# mach_nhan_tin_hieu.net
KiCad netlist of a schematic drawn in Altium Designer
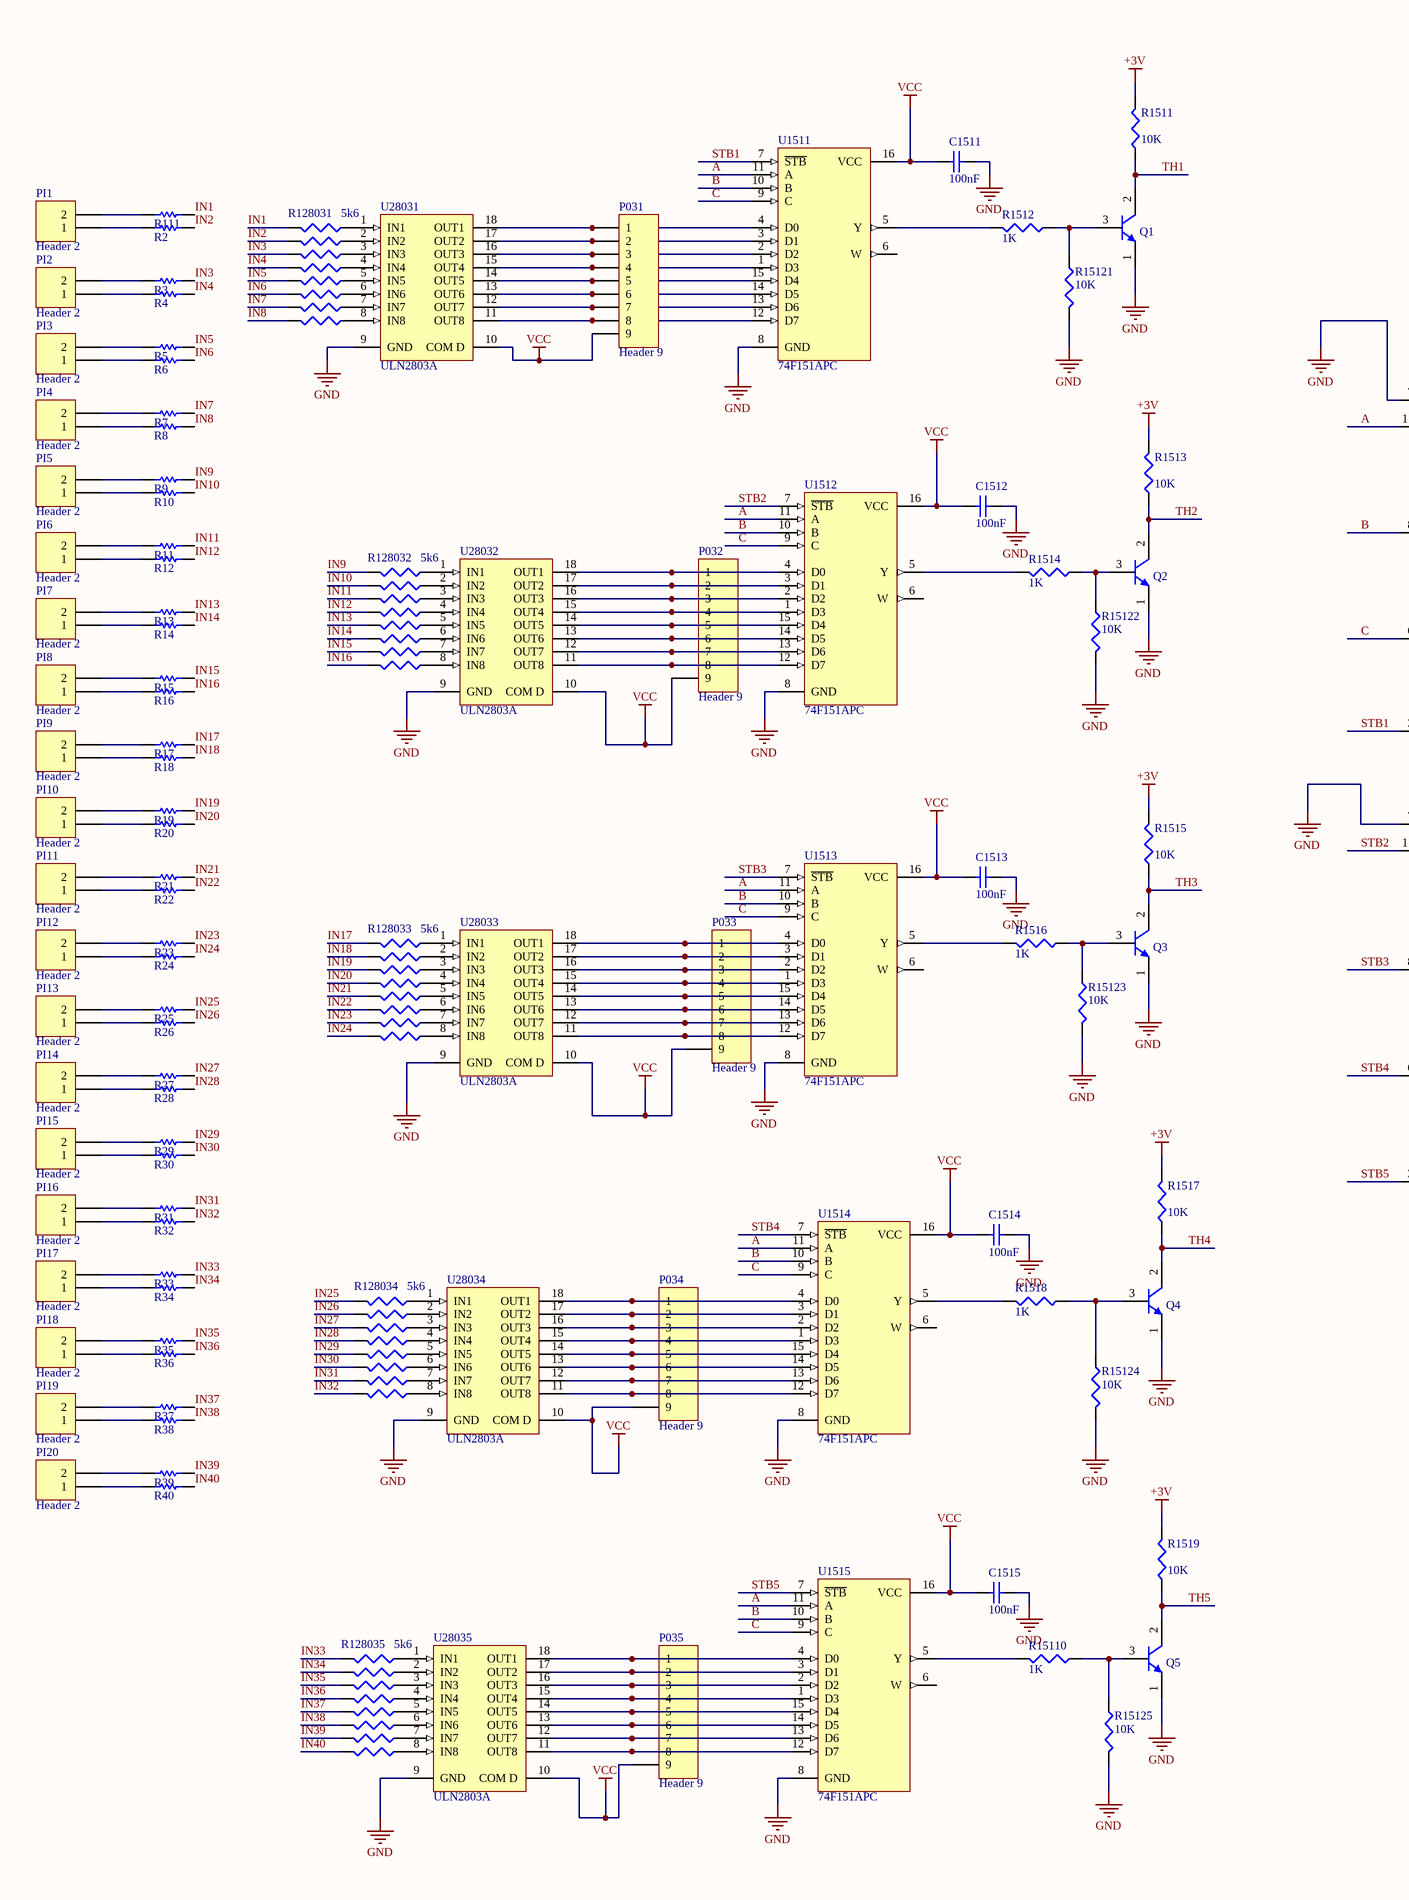
[diagram p0: mach nhan tin hieu.SchDoc, left]
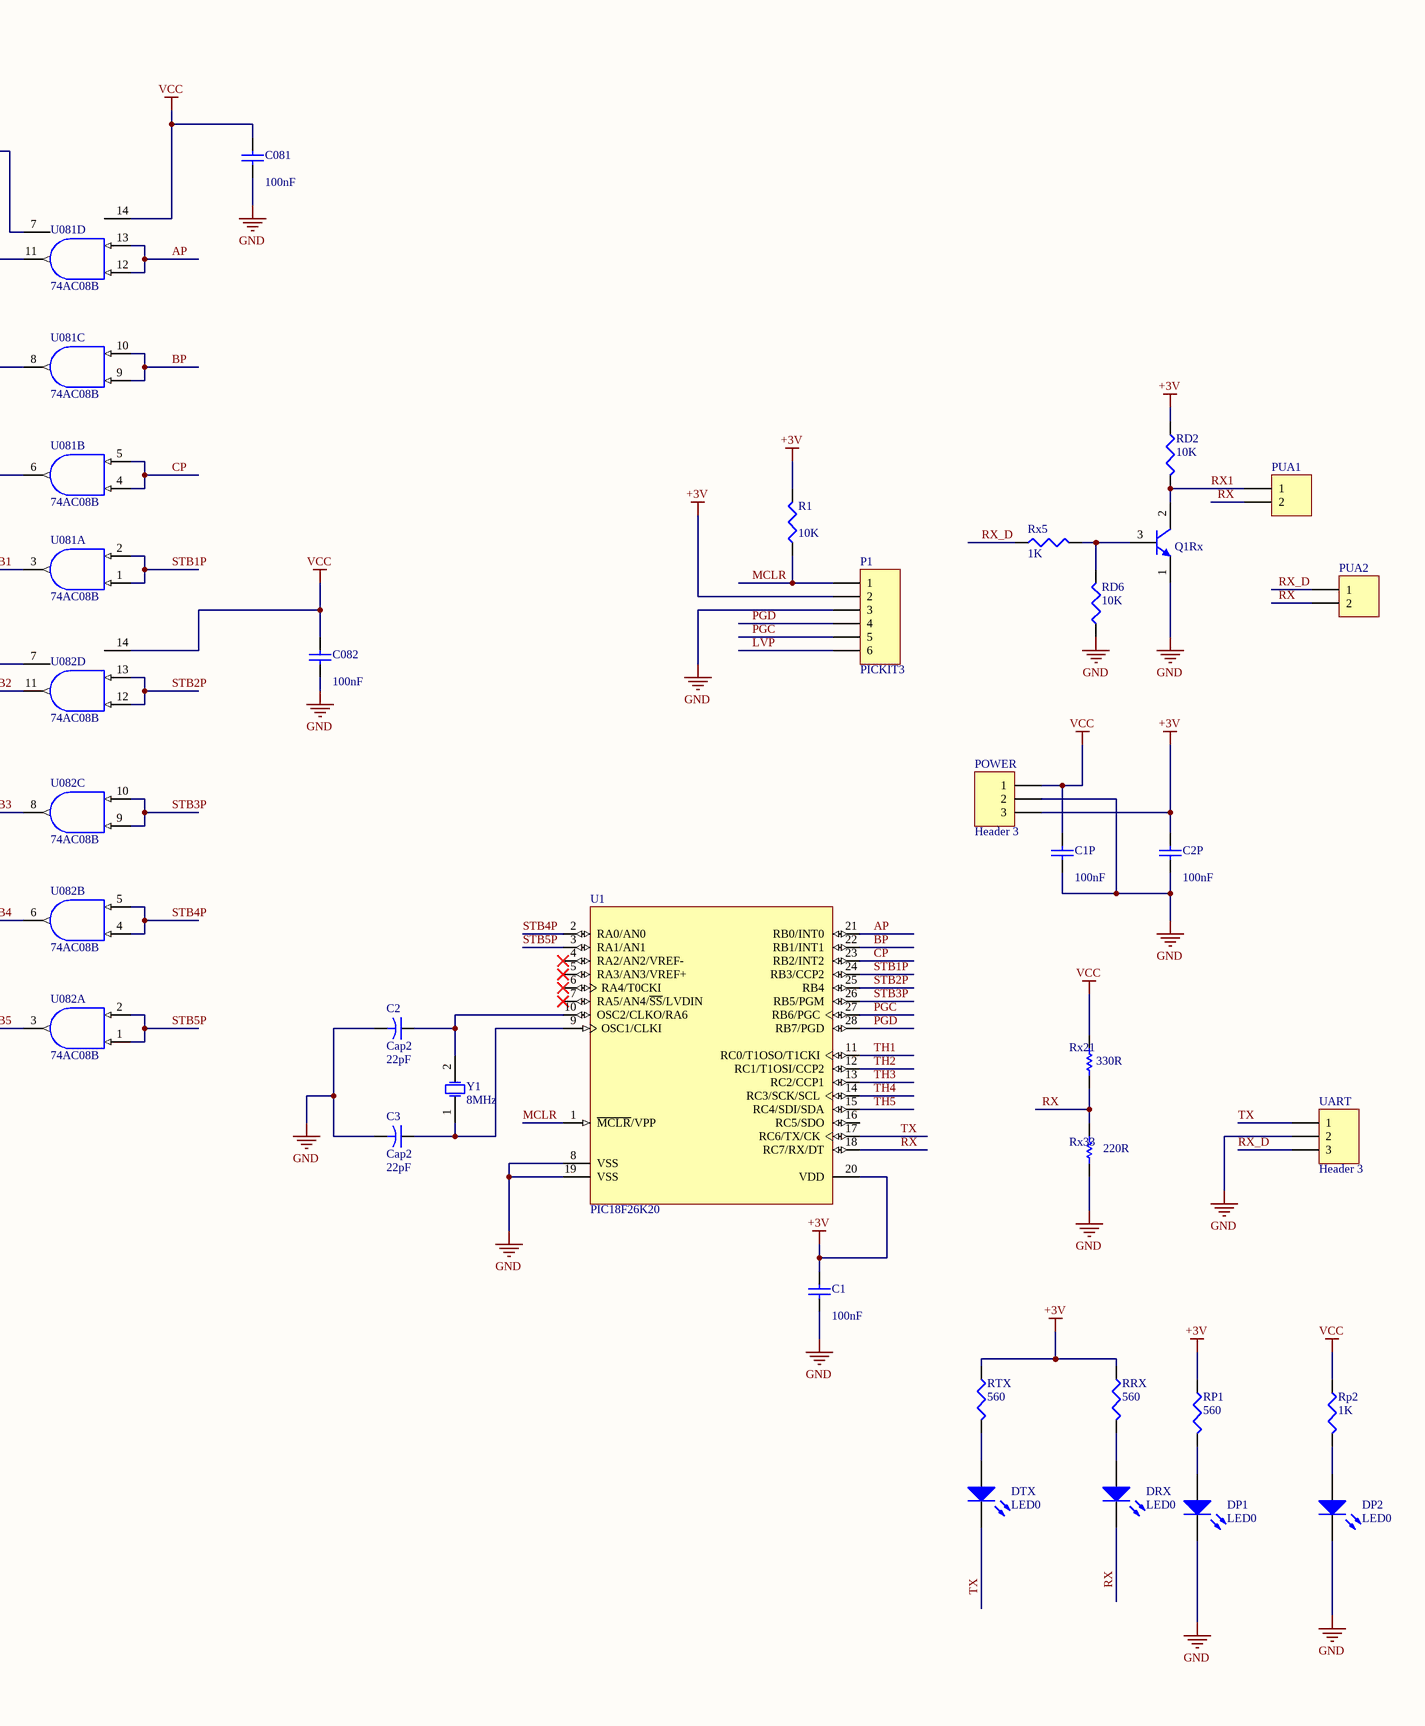
[diagram p1: mach nhan tin hieu.SchDoc, right]

(export (version "E")
  (design (tool "Eeschema 10.0.6"))
  (components
    (comp (ref "C1")
      (value "100nF")
      (footprint "Device:tu_gom")
      (description "Capacitor")
      (fields (field (name "Comment") "Cap") (field (name "PUBLISHER") "Altium Limited"))
      (libsource (lib "Miscellaneous Devices") (part "Cap"))
    )
    (comp (ref "C1P")
      (value "100nF")
      (footprint "Device:tu_gom")
      (description "Capacitor")
      (fields (field (name "Comment") "Cap") (field (name "PUBLISHER") "Altium Limited"))
      (libsource (lib "Miscellaneous Devices") (part "Cap"))
    )
    (comp (ref "C2")
      (value "Cap2")
      (footprint "Device:tu_gom")
      (description "Capacitor")
      (fields (field (name "ALTIUM_VALUE") "22pF") (field (name "PUBLISHER") "Altium Limited"))
      (libsource (lib "Miscellaneous Devices") (part "Cap2"))
    )
    (comp (ref "C2P")
      (value "100nF")
      (footprint "Device:tu_gom")
      (description "Capacitor")
      (fields (field (name "Comment") "Cap") (field (name "PUBLISHER") "Altium Limited"))
      (libsource (lib "Miscellaneous Devices") (part "Cap"))
    )
    (comp (ref "C3")
      (value "Cap2")
      (footprint "Device:tu_gom")
      (description "Capacitor")
      (fields (field (name "ALTIUM_VALUE") "22pF") (field (name "PUBLISHER") "Altium Limited"))
      (libsource (lib "Miscellaneous Devices") (part "Cap2"))
    )
    (comp (ref "C081")
      (value "100nF")
      (footprint "Device:tu_gom")
      (description "Capacitor")
      (fields (field (name "Comment") "Cap") (field (name "PUBLISHER") "Altium Limited"))
      (libsource (lib "Miscellaneous Devices") (part "Cap"))
    )
    (comp (ref "C082")
      (value "100nF")
      (footprint "Device:tu_gom")
      (description "Capacitor")
      (fields (field (name "Comment") "Cap") (field (name "PUBLISHER") "Altium Limited"))
      (libsource (lib "Miscellaneous Devices") (part "Cap"))
    )
    (comp (ref "C1511")
      (value "100nF")
      (footprint "Device:tu_gom")
      (description "Capacitor")
      (fields (field (name "Comment") "Cap") (field (name "PUBLISHER") "Altium Limited"))
      (libsource (lib "Miscellaneous Devices") (part "Cap"))
    )
    (comp (ref "C1512")
      (value "100nF")
      (footprint "Device:tu_gom")
      (description "Capacitor")
      (fields (field (name "Comment") "Cap") (field (name "PUBLISHER") "Altium Limited"))
      (libsource (lib "Miscellaneous Devices") (part "Cap"))
    )
    (comp (ref "C1513")
      (value "100nF")
      (footprint "Device:tu_gom")
      (description "Capacitor")
      (fields (field (name "Comment") "Cap") (field (name "PUBLISHER") "Altium Limited"))
      (libsource (lib "Miscellaneous Devices") (part "Cap"))
    )
    (comp (ref "C1514")
      (value "100nF")
      (footprint "Device:tu_gom")
      (description "Capacitor")
      (fields (field (name "Comment") "Cap") (field (name "PUBLISHER") "Altium Limited"))
      (libsource (lib "Miscellaneous Devices") (part "Cap"))
    )
    (comp (ref "C1515")
      (value "100nF")
      (footprint "Device:tu_gom")
      (description "Capacitor")
      (fields (field (name "Comment") "Cap") (field (name "PUBLISHER") "Altium Limited"))
      (libsource (lib "Miscellaneous Devices") (part "Cap"))
    )
    (comp (ref "DP1")
      (value "LED0")
      (footprint "Device:LED_3")
      (description "Typical INFRARED GaAs LED")
      (fields (field (name "PUBLISHER") "Altium Limited"))
      (libsource (lib "Miscellaneous Devices") (part "LED0"))
    )
    (comp (ref "DP2")
      (value "LED0")
      (footprint "Device:LED_3")
      (description "Typical INFRARED GaAs LED")
      (fields (field (name "PUBLISHER") "Altium Limited"))
      (libsource (lib "Miscellaneous Devices") (part "LED0"))
    )
    (comp (ref "DRX")
      (value "LED0")
      (footprint "Device:LED_3")
      (description "Typical INFRARED GaAs LED")
      (fields (field (name "PUBLISHER") "Altium Limited"))
      (libsource (lib "Miscellaneous Devices") (part "LED0"))
    )
    (comp (ref "DTX")
      (value "LED0")
      (footprint "Device:LED_3")
      (description "Typical INFRARED GaAs LED")
      (fields (field (name "PUBLISHER") "Altium Limited"))
      (libsource (lib "Miscellaneous Devices") (part "LED0"))
    )
    (comp (ref "P1")
      (value "PICKIT3")
      (footprint "HDR1X6")
      (description "Header, 6-Pin")
      (fields (field (name "PUBLISHER") "Altium Limited"))
      (libsource (lib "Miscellaneous Connectors") (part "Header 6"))
    )
    (comp (ref "P031")
      (value "Header 9")
      (footprint "HDR1X9")
      (description "Header, 9-Pin")
      (fields (field (name "PUBLISHER") "Altium Limited"))
      (libsource (lib "Miscellaneous Connectors") (part "Header 9"))
    )
    (comp (ref "P032")
      (value "Header 9")
      (footprint "HDR1X9")
      (description "Header, 9-Pin")
      (fields (field (name "PUBLISHER") "Altium Limited"))
      (libsource (lib "Miscellaneous Connectors") (part "Header 9"))
    )
    (comp (ref "P033")
      (value "Header 9")
      (footprint "HDR1X9")
      (description "Header, 9-Pin")
      (fields (field (name "PUBLISHER") "Altium Limited"))
      (libsource (lib "Miscellaneous Connectors") (part "Header 9"))
    )
    (comp (ref "P034")
      (value "Header 9")
      (footprint "HDR1X9")
      (description "Header, 9-Pin")
      (fields (field (name "PUBLISHER") "Altium Limited"))
      (libsource (lib "Miscellaneous Connectors") (part "Header 9"))
    )
    (comp (ref "P035")
      (value "Header 9")
      (footprint "HDR1X9")
      (description "Header, 9-Pin")
      (fields (field (name "PUBLISHER") "Altium Limited"))
      (libsource (lib "Miscellaneous Connectors") (part "Header 9"))
    )
    (comp (ref "PI1")
      (value "Header 2")
      (footprint "Device:Header_nguon_20A")
      (description "Header, 2-Pin")
      (fields (field (name "PUBLISHER") "Altium Limited"))
      (libsource (lib "Miscellaneous Connectors") (part "Header 2"))
    )
    (comp (ref "PI2")
      (value "Header 2")
      (footprint "Device:Header_nguon_20A")
      (description "Header, 2-Pin")
      (fields (field (name "PUBLISHER") "Altium Limited"))
      (libsource (lib "Miscellaneous Connectors") (part "Header 2"))
    )
    (comp (ref "PI3")
      (value "Header 2")
      (footprint "Device:Header_nguon_20A")
      (description "Header, 2-Pin")
      (fields (field (name "PUBLISHER") "Altium Limited"))
      (libsource (lib "Miscellaneous Connectors") (part "Header 2"))
    )
    (comp (ref "PI4")
      (value "Header 2")
      (footprint "Device:Header_nguon_20A")
      (description "Header, 2-Pin")
      (fields (field (name "PUBLISHER") "Altium Limited"))
      (libsource (lib "Miscellaneous Connectors") (part "Header 2"))
    )
    (comp (ref "PI5")
      (value "Header 2")
      (footprint "Device:Header_nguon_20A")
      (description "Header, 2-Pin")
      (fields (field (name "PUBLISHER") "Altium Limited"))
      (libsource (lib "Miscellaneous Connectors") (part "Header 2"))
    )
    (comp (ref "PI6")
      (value "Header 2")
      (footprint "Device:Header_nguon_20A")
      (description "Header, 2-Pin")
      (fields (field (name "PUBLISHER") "Altium Limited"))
      (libsource (lib "Miscellaneous Connectors") (part "Header 2"))
    )
    (comp (ref "PI7")
      (value "Header 2")
      (footprint "Device:Header_nguon_20A")
      (description "Header, 2-Pin")
      (fields (field (name "PUBLISHER") "Altium Limited"))
      (libsource (lib "Miscellaneous Connectors") (part "Header 2"))
    )
    (comp (ref "PI8")
      (value "Header 2")
      (footprint "Device:Header_nguon_20A")
      (description "Header, 2-Pin")
      (fields (field (name "PUBLISHER") "Altium Limited"))
      (libsource (lib "Miscellaneous Connectors") (part "Header 2"))
    )
    (comp (ref "PI9")
      (value "Header 2")
      (footprint "Device:Header_nguon_20A")
      (description "Header, 2-Pin")
      (fields (field (name "PUBLISHER") "Altium Limited"))
      (libsource (lib "Miscellaneous Connectors") (part "Header 2"))
    )
    (comp (ref "PI10")
      (value "Header 2")
      (footprint "Device:Header_nguon_20A")
      (description "Header, 2-Pin")
      (fields (field (name "PUBLISHER") "Altium Limited"))
      (libsource (lib "Miscellaneous Connectors") (part "Header 2"))
    )
    (comp (ref "PI11")
      (value "Header 2")
      (footprint "Device:Header_nguon_20A")
      (description "Header, 2-Pin")
      (fields (field (name "PUBLISHER") "Altium Limited"))
      (libsource (lib "Miscellaneous Connectors") (part "Header 2"))
    )
    (comp (ref "PI12")
      (value "Header 2")
      (footprint "Device:Header_nguon_20A")
      (description "Header, 2-Pin")
      (fields (field (name "PUBLISHER") "Altium Limited"))
      (libsource (lib "Miscellaneous Connectors") (part "Header 2"))
    )
    (comp (ref "PI13")
      (value "Header 2")
      (footprint "Device:Header_nguon_20A")
      (description "Header, 2-Pin")
      (fields (field (name "PUBLISHER") "Altium Limited"))
      (libsource (lib "Miscellaneous Connectors") (part "Header 2"))
    )
    (comp (ref "PI14")
      (value "Header 2")
      (footprint "Device:Header_nguon_20A")
      (description "Header, 2-Pin")
      (fields (field (name "PUBLISHER") "Altium Limited"))
      (libsource (lib "Miscellaneous Connectors") (part "Header 2"))
    )
    (comp (ref "PI15")
      (value "Header 2")
      (footprint "Device:Header_nguon_20A")
      (description "Header, 2-Pin")
      (fields (field (name "PUBLISHER") "Altium Limited"))
      (libsource (lib "Miscellaneous Connectors") (part "Header 2"))
    )
    (comp (ref "PI16")
      (value "Header 2")
      (footprint "Device:Header_nguon_20A")
      (description "Header, 2-Pin")
      (fields (field (name "PUBLISHER") "Altium Limited"))
      (libsource (lib "Miscellaneous Connectors") (part "Header 2"))
    )
    (comp (ref "PI17")
      (value "Header 2")
      (footprint "Device:Header_nguon_20A")
      (description "Header, 2-Pin")
      (fields (field (name "PUBLISHER") "Altium Limited"))
      (libsource (lib "Miscellaneous Connectors") (part "Header 2"))
    )
    (comp (ref "PI18")
      (value "Header 2")
      (footprint "Device:Header_nguon_20A")
      (description "Header, 2-Pin")
      (fields (field (name "PUBLISHER") "Altium Limited"))
      (libsource (lib "Miscellaneous Connectors") (part "Header 2"))
    )
    (comp (ref "PI19")
      (value "Header 2")
      (footprint "Device:Header_nguon_20A")
      (description "Header, 2-Pin")
      (fields (field (name "PUBLISHER") "Altium Limited"))
      (libsource (lib "Miscellaneous Connectors") (part "Header 2"))
    )
    (comp (ref "PI20")
      (value "Header 2")
      (footprint "Device:Header_nguon_20A")
      (description "Header, 2-Pin")
      (fields (field (name "PUBLISHER") "Altium Limited"))
      (libsource (lib "Miscellaneous Connectors") (part "Header 2"))
    )
    (comp (ref "POWER")
      (value "Header 3")
      (footprint "Device:HEADER3")
      (description "Header, 3-Pin")
      (fields (field (name "PUBLISHER") "Altium Limited"))
      (libsource (lib "Miscellaneous Connectors") (part "Header 3"))
    )
    (comp (ref "PUA1")
      (value "Header 2")
      (footprint "HDR1X2")
      (description "Header, 2-Pin")
      (fields (field (name "PUBLISHER") "Altium Limited"))
      (libsource (lib "") (part "Header 2_1"))
    )
    (comp (ref "PUA2")
      (value "Header 2")
      (footprint "HDR1X2")
      (description "Header, 2-Pin")
      (fields (field (name "PUBLISHER") "Altium Limited"))
      (libsource (lib "") (part "Header 2_1"))
    )
    (comp (ref "Q1")
      (value "C1815")
      (footprint "Device:C1815")
      (libsource (lib "Device_Component") (part "C1815"))
    )
    (comp (ref "Q1Rx")
      (value "C1815")
      (footprint "Device:C1815")
      (libsource (lib "Device_Component") (part "C1815"))
    )
    (comp (ref "Q2")
      (value "C1815")
      (footprint "Device:C1815")
      (libsource (lib "Device_Component") (part "C1815"))
    )
    (comp (ref "Q3")
      (value "C1815")
      (footprint "Device:C1815")
      (libsource (lib "Device_Component") (part "C1815"))
    )
    (comp (ref "Q4")
      (value "C1815")
      (footprint "Device:C1815")
      (libsource (lib "Device_Component") (part "C1815"))
    )
    (comp (ref "Q5")
      (value "C1815")
      (footprint "Device:C1815")
      (libsource (lib "Device_Component") (part "C1815"))
    )
    (comp (ref "R1")
      (value "10K")
      (footprint "Device:R_Nor")
      (description "Resistor")
      (fields (field (name "Comment") "Res3") (field (name "PUBLISHER") "Altium Limited"))
      (libsource (lib "Miscellaneous Devices") (part "Res3"))
    )
    (comp (ref "R2")
      (value "Res")
      (footprint "Device:R_Nor")
      (libsource (lib "Device_Component") (part "Res"))
    )
    (comp (ref "R3")
      (value "Res")
      (footprint "Device:R_Nor")
      (libsource (lib "Device_Component") (part "Res"))
    )
    (comp (ref "R4")
      (value "Res")
      (footprint "Device:R_Nor")
      (libsource (lib "Device_Component") (part "Res"))
    )
    (comp (ref "R5")
      (value "Res")
      (footprint "Device:R_Nor")
      (libsource (lib "Device_Component") (part "Res"))
    )
    (comp (ref "R6")
      (value "Res")
      (footprint "Device:R_Nor")
      (libsource (lib "Device_Component") (part "Res"))
    )
    (comp (ref "R7")
      (value "Res")
      (footprint "Device:R_Nor")
      (libsource (lib "Device_Component") (part "Res"))
    )
    (comp (ref "R8")
      (value "Res")
      (footprint "Device:R_Nor")
      (libsource (lib "Device_Component") (part "Res"))
    )
    (comp (ref "R9")
      (value "Res")
      (footprint "Device:R_Nor")
      (libsource (lib "Device_Component") (part "Res"))
    )
    (comp (ref "R10")
      (value "Res")
      (footprint "Device:R_Nor")
      (libsource (lib "Device_Component") (part "Res"))
    )
    (comp (ref "R11")
      (value "Res")
      (footprint "Device:R_Nor")
      (libsource (lib "Device_Component") (part "Res"))
    )
    (comp (ref "R12")
      (value "Res")
      (footprint "Device:R_Nor")
      (libsource (lib "Device_Component") (part "Res"))
    )
    (comp (ref "R13")
      (value "Res")
      (footprint "Device:R_Nor")
      (libsource (lib "Device_Component") (part "Res"))
    )
    (comp (ref "R14")
      (value "Res")
      (footprint "Device:R_Nor")
      (libsource (lib "Device_Component") (part "Res"))
    )
    (comp (ref "R15")
      (value "Res")
      (footprint "Device:R_Nor")
      (libsource (lib "Device_Component") (part "Res"))
    )
    (comp (ref "R16")
      (value "Res")
      (footprint "Device:R_Nor")
      (libsource (lib "Device_Component") (part "Res"))
    )
    (comp (ref "R17")
      (value "Res")
      (footprint "Device:R_Nor")
      (libsource (lib "Device_Component") (part "Res"))
    )
    (comp (ref "R18")
      (value "Res")
      (footprint "Device:R_Nor")
      (libsource (lib "Device_Component") (part "Res"))
    )
    (comp (ref "R19")
      (value "Res")
      (footprint "Device:R_Nor")
      (libsource (lib "Device_Component") (part "Res"))
    )
    (comp (ref "R20")
      (value "Res")
      (footprint "Device:R_Nor")
      (libsource (lib "Device_Component") (part "Res"))
    )
    (comp (ref "R21")
      (value "Res")
      (footprint "Device:R_Nor")
      (libsource (lib "Device_Component") (part "Res"))
    )
    (comp (ref "R22")
      (value "Res")
      (footprint "Device:R_Nor")
      (libsource (lib "Device_Component") (part "Res"))
    )
    (comp (ref "R23")
      (value "Res")
      (footprint "Device:R_Nor")
      (libsource (lib "Device_Component") (part "Res"))
    )
    (comp (ref "R24")
      (value "Res")
      (footprint "Device:R_Nor")
      (libsource (lib "Device_Component") (part "Res"))
    )
    (comp (ref "R25")
      (value "Res")
      (footprint "Device:R_Nor")
      (libsource (lib "Device_Component") (part "Res"))
    )
    (comp (ref "R26")
      (value "Res")
      (footprint "Device:R_Nor")
      (libsource (lib "Device_Component") (part "Res"))
    )
    (comp (ref "R27")
      (value "Res")
      (footprint "Device:R_Nor")
      (libsource (lib "Device_Component") (part "Res"))
    )
    (comp (ref "R28")
      (value "Res")
      (footprint "Device:R_Nor")
      (libsource (lib "Device_Component") (part "Res"))
    )
    (comp (ref "R29")
      (value "Res")
      (footprint "Device:R_Nor")
      (libsource (lib "Device_Component") (part "Res"))
    )
    (comp (ref "R30")
      (value "Res")
      (footprint "Device:R_Nor")
      (libsource (lib "Device_Component") (part "Res"))
    )
    (comp (ref "R31")
      (value "Res")
      (footprint "Device:R_Nor")
      (libsource (lib "Device_Component") (part "Res"))
    )
    (comp (ref "R32")
      (value "Res")
      (footprint "Device:R_Nor")
      (libsource (lib "Device_Component") (part "Res"))
    )
    (comp (ref "R33")
      (value "Res")
      (footprint "Device:R_Nor")
      (libsource (lib "Device_Component") (part "Res"))
    )
    (comp (ref "R34")
      (value "Res")
      (footprint "Device:R_Nor")
      (libsource (lib "Device_Component") (part "Res"))
    )
    (comp (ref "R35")
      (value "Res")
      (footprint "Device:R_Nor")
      (libsource (lib "Device_Component") (part "Res"))
    )
    (comp (ref "R36")
      (value "Res")
      (footprint "Device:R_Nor")
      (libsource (lib "Device_Component") (part "Res"))
    )
    (comp (ref "R37")
      (value "Res")
      (footprint "Device:R_Nor")
      (libsource (lib "Device_Component") (part "Res"))
    )
    (comp (ref "R38")
      (value "Res")
      (footprint "Device:R_Nor")
      (libsource (lib "Device_Component") (part "Res"))
    )
    (comp (ref "R39")
      (value "Res")
      (footprint "Device:R_Nor")
      (libsource (lib "Device_Component") (part "Res"))
    )
    (comp (ref "R40")
      (value "Res")
      (footprint "Device:R_Nor")
      (libsource (lib "Device_Component") (part "Res"))
    )
    (comp (ref "R111")
      (value "Res")
      (footprint "Device:R_Nor")
      (libsource (lib "Device_Component") (part "Res"))
    )
    (comp (ref "R1511")
      (value "10K")
      (footprint "Device:R_Nor")
      (description "Resistor")
      (fields (field (name "Comment") "Res3") (field (name "PUBLISHER") "Altium Limited"))
      (libsource (lib "Miscellaneous Devices") (part "Res3"))
    )
    (comp (ref "R1512")
      (value "1K")
      (footprint "Device:R_Nor")
      (description "Resistor")
      (fields (field (name "Comment") "Res3") (field (name "PUBLISHER") "Altium Limited"))
      (libsource (lib "Miscellaneous Devices") (part "Res3"))
    )
    (comp (ref "R1513")
      (value "10K")
      (footprint "Device:R_Nor")
      (description "Resistor")
      (fields (field (name "Comment") "Res3") (field (name "PUBLISHER") "Altium Limited"))
      (libsource (lib "Miscellaneous Devices") (part "Res3"))
    )
    (comp (ref "R1514")
      (value "1K")
      (footprint "Device:R_Nor")
      (description "Resistor")
      (fields (field (name "Comment") "Res3") (field (name "PUBLISHER") "Altium Limited"))
      (libsource (lib "Miscellaneous Devices") (part "Res3"))
    )
    (comp (ref "R1515")
      (value "10K")
      (footprint "Device:R_Nor")
      (description "Resistor")
      (fields (field (name "Comment") "Res3") (field (name "PUBLISHER") "Altium Limited"))
      (libsource (lib "Miscellaneous Devices") (part "Res3"))
    )
    (comp (ref "R1516")
      (value "1K")
      (footprint "Device:R_Nor")
      (description "Resistor")
      (fields (field (name "Comment") "Res3") (field (name "PUBLISHER") "Altium Limited"))
      (libsource (lib "Miscellaneous Devices") (part "Res3"))
    )
    (comp (ref "R1517")
      (value "10K")
      (footprint "Device:R_Nor")
      (description "Resistor")
      (fields (field (name "Comment") "Res3") (field (name "PUBLISHER") "Altium Limited"))
      (libsource (lib "Miscellaneous Devices") (part "Res3"))
    )
    (comp (ref "R1518")
      (value "1K")
      (footprint "Device:R_Nor")
      (description "Resistor")
      (fields (field (name "Comment") "Res3") (field (name "PUBLISHER") "Altium Limited"))
      (libsource (lib "Miscellaneous Devices") (part "Res3"))
    )
    (comp (ref "R1519")
      (value "10K")
      (footprint "Device:R_Nor")
      (description "Resistor")
      (fields (field (name "Comment") "Res3") (field (name "PUBLISHER") "Altium Limited"))
      (libsource (lib "Miscellaneous Devices") (part "Res3"))
    )
    (comp (ref "R15110")
      (value "1K")
      (footprint "Device:R_Nor")
      (description "Resistor")
      (fields (field (name "Comment") "Res3") (field (name "PUBLISHER") "Altium Limited"))
      (libsource (lib "Miscellaneous Devices") (part "Res3"))
    )
    (comp (ref "R15121")
      (value "10K")
      (footprint "Device:R_Nor")
      (description "Resistor")
      (fields (field (name "Comment") "Res3") (field (name "PUBLISHER") "Altium Limited"))
      (libsource (lib "Miscellaneous Devices") (part "Res3"))
    )
    (comp (ref "R15122")
      (value "10K")
      (footprint "Device:R_Nor")
      (description "Resistor")
      (fields (field (name "Comment") "Res3") (field (name "PUBLISHER") "Altium Limited"))
      (libsource (lib "Miscellaneous Devices") (part "Res3"))
    )
    (comp (ref "R15123")
      (value "10K")
      (footprint "Device:R_Nor")
      (description "Resistor")
      (fields (field (name "Comment") "Res3") (field (name "PUBLISHER") "Altium Limited"))
      (libsource (lib "Miscellaneous Devices") (part "Res3"))
    )
    (comp (ref "R15124")
      (value "10K")
      (footprint "Device:R_Nor")
      (description "Resistor")
      (fields (field (name "Comment") "Res3") (field (name "PUBLISHER") "Altium Limited"))
      (libsource (lib "Miscellaneous Devices") (part "Res3"))
    )
    (comp (ref "R15125")
      (value "10K")
      (footprint "Device:R_Nor")
      (description "Resistor")
      (fields (field (name "Comment") "Res3") (field (name "PUBLISHER") "Altium Limited"))
      (libsource (lib "Miscellaneous Devices") (part "Res3"))
    )
    (comp (ref "R42802")
      (value "Res3")
      (footprint "Device:R_Nor")
      (description "Resistor")
      (fields (field (name "PUBLISHER") "Altium Limited"))
      (libsource (lib "Miscellaneous Devices") (part "Res3"))
    )
    (comp (ref "R42803")
      (value "Res3")
      (footprint "Device:R_Nor")
      (description "Resistor")
      (fields (field (name "PUBLISHER") "Altium Limited"))
      (libsource (lib "Miscellaneous Devices") (part "Res3"))
    )
    (comp (ref "R42804")
      (value "Res3")
      (footprint "Device:R_Nor")
      (description "Resistor")
      (fields (field (name "PUBLISHER") "Altium Limited"))
      (libsource (lib "Miscellaneous Devices") (part "Res3"))
    )
    (comp (ref "R128031")
      (value "5k6")
      (footprint "Device:R_Nor")
      (description "Resistor")
      (fields (field (name "Comment") "Res3") (field (name "PUBLISHER") "Altium Limited"))
      (libsource (lib "Miscellaneous Devices") (part "Res3"))
    )
    (comp (ref "R128032")
      (value "5k6")
      (footprint "Device:R_Nor")
      (description "Resistor")
      (fields (field (name "Comment") "Res3") (field (name "PUBLISHER") "Altium Limited"))
      (libsource (lib "Miscellaneous Devices") (part "Res3"))
    )
    (comp (ref "R128033")
      (value "5k6")
      (footprint "Device:R_Nor")
      (description "Resistor")
      (fields (field (name "Comment") "Res3") (field (name "PUBLISHER") "Altium Limited"))
      (libsource (lib "Miscellaneous Devices") (part "Res3"))
    )
    (comp (ref "R128034")
      (value "5k6")
      (footprint "Device:R_Nor")
      (description "Resistor")
      (fields (field (name "Comment") "Res3") (field (name "PUBLISHER") "Altium Limited"))
      (libsource (lib "Miscellaneous Devices") (part "Res3"))
    )
    (comp (ref "R128035")
      (value "5k6")
      (footprint "Device:R_Nor")
      (description "Resistor")
      (fields (field (name "Comment") "Res3") (field (name "PUBLISHER") "Altium Limited"))
      (libsource (lib "Miscellaneous Devices") (part "Res3"))
    )
    (comp (ref "R228031")
      (value "Res3")
      (footprint "Device:R_Nor")
      (description "Resistor")
      (fields (field (name "PUBLISHER") "Altium Limited"))
      (libsource (lib "Miscellaneous Devices") (part "Res3"))
    )
    (comp (ref "R228032")
      (value "Res3")
      (footprint "Device:R_Nor")
      (description "Resistor")
      (fields (field (name "PUBLISHER") "Altium Limited"))
      (libsource (lib "Miscellaneous Devices") (part "Res3"))
    )
    (comp (ref "R228033")
      (value "Res3")
      (footprint "Device:R_Nor")
      (description "Resistor")
      (fields (field (name "PUBLISHER") "Altium Limited"))
      (libsource (lib "Miscellaneous Devices") (part "Res3"))
    )
    (comp (ref "R228034")
      (value "Res3")
      (footprint "Device:R_Nor")
      (description "Resistor")
      (fields (field (name "PUBLISHER") "Altium Limited"))
      (libsource (lib "Miscellaneous Devices") (part "Res3"))
    )
    (comp (ref "R228035")
      (value "Res3")
      (footprint "Device:R_Nor")
      (description "Resistor")
      (fields (field (name "PUBLISHER") "Altium Limited"))
      (libsource (lib "Miscellaneous Devices") (part "Res3"))
    )
    (comp (ref "R328031")
      (value "Res3")
      (footprint "Device:R_Nor")
      (description "Resistor")
      (fields (field (name "PUBLISHER") "Altium Limited"))
      (libsource (lib "Miscellaneous Devices") (part "Res3"))
    )
    (comp (ref "R328032")
      (value "Res3")
      (footprint "Device:R_Nor")
      (description "Resistor")
      (fields (field (name "PUBLISHER") "Altium Limited"))
      (libsource (lib "Miscellaneous Devices") (part "Res3"))
    )
    (comp (ref "R328033")
      (value "Res3")
      (footprint "Device:R_Nor")
      (description "Resistor")
      (fields (field (name "PUBLISHER") "Altium Limited"))
      (libsource (lib "Miscellaneous Devices") (part "Res3"))
    )
    (comp (ref "R328034")
      (value "Res3")
      (footprint "Device:R_Nor")
      (description "Resistor")
      (fields (field (name "PUBLISHER") "Altium Limited"))
      (libsource (lib "Miscellaneous Devices") (part "Res3"))
    )
    (comp (ref "R328035")
      (value "Res3")
      (footprint "Device:R_Nor")
      (description "Resistor")
      (fields (field (name "PUBLISHER") "Altium Limited"))
      (libsource (lib "Miscellaneous Devices") (part "Res3"))
    )
    (comp (ref "R428031")
      (value "Res3")
      (footprint "Device:R_Nor")
      (description "Resistor")
      (fields (field (name "PUBLISHER") "Altium Limited"))
      (libsource (lib "Miscellaneous Devices") (part "Res3"))
    )
    (comp (ref "R428035")
      (value "Res3")
      (footprint "Device:R_Nor")
      (description "Resistor")
      (fields (field (name "PUBLISHER") "Altium Limited"))
      (libsource (lib "Miscellaneous Devices") (part "Res3"))
    )
    (comp (ref "R528031")
      (value "Res3")
      (footprint "Device:R_Nor")
      (description "Resistor")
      (fields (field (name "PUBLISHER") "Altium Limited"))
      (libsource (lib "Miscellaneous Devices") (part "Res3"))
    )
    (comp (ref "R528032")
      (value "Res3")
      (footprint "Device:R_Nor")
      (description "Resistor")
      (fields (field (name "PUBLISHER") "Altium Limited"))
      (libsource (lib "Miscellaneous Devices") (part "Res3"))
    )
    (comp (ref "R528033")
      (value "Res3")
      (footprint "Device:R_Nor")
      (description "Resistor")
      (fields (field (name "PUBLISHER") "Altium Limited"))
      (libsource (lib "Miscellaneous Devices") (part "Res3"))
    )
    (comp (ref "R528034")
      (value "Res3")
      (footprint "Device:R_Nor")
      (description "Resistor")
      (fields (field (name "PUBLISHER") "Altium Limited"))
      (libsource (lib "Miscellaneous Devices") (part "Res3"))
    )
    (comp (ref "R528035")
      (value "Res3")
      (footprint "Device:R_Nor")
      (description "Resistor")
      (fields (field (name "PUBLISHER") "Altium Limited"))
      (libsource (lib "Miscellaneous Devices") (part "Res3"))
    )
    (comp (ref "R628031")
      (value "Res3")
      (footprint "Device:R_Nor")
      (description "Resistor")
      (fields (field (name "PUBLISHER") "Altium Limited"))
      (libsource (lib "Miscellaneous Devices") (part "Res3"))
    )
    (comp (ref "R628032")
      (value "Res3")
      (footprint "Device:R_Nor")
      (description "Resistor")
      (fields (field (name "PUBLISHER") "Altium Limited"))
      (libsource (lib "Miscellaneous Devices") (part "Res3"))
    )
    (comp (ref "R628033")
      (value "Res3")
      (footprint "Device:R_Nor")
      (description "Resistor")
      (fields (field (name "PUBLISHER") "Altium Limited"))
      (libsource (lib "Miscellaneous Devices") (part "Res3"))
    )
    (comp (ref "R628034")
      (value "Res3")
      (footprint "Device:R_Nor")
      (description "Resistor")
      (fields (field (name "PUBLISHER") "Altium Limited"))
      (libsource (lib "Miscellaneous Devices") (part "Res3"))
    )
    (comp (ref "R628035")
      (value "Res3")
      (footprint "Device:R_Nor")
      (description "Resistor")
      (fields (field (name "PUBLISHER") "Altium Limited"))
      (libsource (lib "Miscellaneous Devices") (part "Res3"))
    )
    (comp (ref "R728031")
      (value "Res3")
      (footprint "Device:R_Nor")
      (description "Resistor")
      (fields (field (name "PUBLISHER") "Altium Limited"))
      (libsource (lib "Miscellaneous Devices") (part "Res3"))
    )
    (comp (ref "R728032")
      (value "Res3")
      (footprint "Device:R_Nor")
      (description "Resistor")
      (fields (field (name "PUBLISHER") "Altium Limited"))
      (libsource (lib "Miscellaneous Devices") (part "Res3"))
    )
    (comp (ref "R728033")
      (value "Res3")
      (footprint "Device:R_Nor")
      (description "Resistor")
      (fields (field (name "PUBLISHER") "Altium Limited"))
      (libsource (lib "Miscellaneous Devices") (part "Res3"))
    )
    (comp (ref "R728034")
      (value "Res3")
      (footprint "Device:R_Nor")
      (description "Resistor")
      (fields (field (name "PUBLISHER") "Altium Limited"))
      (libsource (lib "Miscellaneous Devices") (part "Res3"))
    )
    (comp (ref "R728035")
      (value "Res3")
      (footprint "Device:R_Nor")
      (description "Resistor")
      (fields (field (name "PUBLISHER") "Altium Limited"))
      (libsource (lib "Miscellaneous Devices") (part "Res3"))
    )
    (comp (ref "R828031")
      (value "Res3")
      (footprint "Device:R_Nor")
      (description "Resistor")
      (fields (field (name "PUBLISHER") "Altium Limited"))
      (libsource (lib "Miscellaneous Devices") (part "Res3"))
    )
    (comp (ref "R828032")
      (value "Res3")
      (footprint "Device:R_Nor")
      (description "Resistor")
      (fields (field (name "PUBLISHER") "Altium Limited"))
      (libsource (lib "Miscellaneous Devices") (part "Res3"))
    )
    (comp (ref "R828033")
      (value "Res3")
      (footprint "Device:R_Nor")
      (description "Resistor")
      (fields (field (name "PUBLISHER") "Altium Limited"))
      (libsource (lib "Miscellaneous Devices") (part "Res3"))
    )
    (comp (ref "R828034")
      (value "Res3")
      (footprint "Device:R_Nor")
      (description "Resistor")
      (fields (field (name "PUBLISHER") "Altium Limited"))
      (libsource (lib "Miscellaneous Devices") (part "Res3"))
    )
    (comp (ref "R828035")
      (value "Res3")
      (footprint "Device:R_Nor")
      (description "Resistor")
      (fields (field (name "PUBLISHER") "Altium Limited"))
      (libsource (lib "Miscellaneous Devices") (part "Res3"))
    )
    (comp (ref "RD2")
      (value "10K")
      (footprint "Device:R_Nor")
      (description "Resistor")
      (fields (field (name "Comment") "Res3") (field (name "PUBLISHER") "Altium Limited"))
      (libsource (lib "Miscellaneous Devices") (part "Res3"))
    )
    (comp (ref "RD6")
      (value "10K")
      (footprint "Device:R_Nor")
      (description "Resistor")
      (fields (field (name "Comment") "Res3") (field (name "PUBLISHER") "Altium Limited"))
      (libsource (lib "Miscellaneous Devices") (part "Res3"))
    )
    (comp (ref "RP1")
      (value "560")
      (footprint "Device:R_Nor")
      (description "Resistor")
      (fields (field (name "Comment") "Res3") (field (name "PUBLISHER") "Altium Limited"))
      (libsource (lib "Miscellaneous Devices") (part "Res3"))
    )
    (comp (ref "Rp2")
      (value "1K")
      (footprint "Device:R_Nor")
      (description "Resistor")
      (fields (field (name "Comment") "Res3") (field (name "PUBLISHER") "Altium Limited"))
      (libsource (lib "Miscellaneous Devices") (part "Res3"))
    )
    (comp (ref "RRX")
      (value "560")
      (footprint "Device:R_Nor")
      (description "Resistor")
      (fields (field (name "Comment") "Res3") (field (name "PUBLISHER") "Altium Limited"))
      (libsource (lib "Miscellaneous Devices") (part "Res3"))
    )
    (comp (ref "RTX")
      (value "560")
      (footprint "Device:R_Nor")
      (description "Resistor")
      (fields (field (name "Comment") "Res3") (field (name "PUBLISHER") "Altium Limited"))
      (libsource (lib "Miscellaneous Devices") (part "Res3"))
    )
    (comp (ref "Rx5")
      (value "1K")
      (footprint "Device:R_Nor")
      (description "Resistor")
      (fields (field (name "Comment") "Res3") (field (name "PUBLISHER") "Altium Limited"))
      (libsource (lib "Miscellaneous Devices") (part "Res3"))
    )
    (comp (ref "Rx21")
      (value "330R")
      (footprint "Device:R_Nor")
      (libsource (lib "Device_Component") (part "Res"))
    )
    (comp (ref "Rx33")
      (value "220R")
      (footprint "Device:R_Nor")
      (libsource (lib "Device_Component") (part "Res"))
    )
    (comp (ref "U1")
      (value "PIC18F26K20")
      (footprint "SOIC300-28_N")
      (fields (field (name "PUBLISHER") "Altium Limited"))
      (libsource (lib "Microchip Microcontroller 8-Bit PIC18") (part "PIC18F242-E/SO"))
    )
    (comp (ref "U081")
      (value "74AC08B")
      (footprint "DIP14")
      (description "Quad 2-Input AND Gate")
      (fields (field (name "PUBLISHER") "Altium Limited"))
      (libsource (lib "ST Logic Gate") (part "74AC08B"))
    )
    (comp (ref "U082")
      (value "74AC08B")
      (footprint "DIP14")
      (description "Quad 2-Input AND Gate")
      (fields (field (name "PUBLISHER") "Altium Limited"))
      (libsource (lib "ST Logic Gate") (part "74AC08B"))
    )
    (comp (ref "U1511")
      (value "74F151APC")
      (footprint "N16E")
      (description "8-Input Multiplexer")
      (fields (field (name "PUBLISHER") "Altium Limited"))
      (libsource (lib "NSC Logic Multiplexer") (part "74F151APC"))
    )
    (comp (ref "U1512")
      (value "74F151APC")
      (footprint "N16E")
      (description "8-Input Multiplexer")
      (fields (field (name "PUBLISHER") "Altium Limited"))
      (libsource (lib "NSC Logic Multiplexer") (part "74F151APC"))
    )
    (comp (ref "U1513")
      (value "74F151APC")
      (footprint "N16E")
      (description "8-Input Multiplexer")
      (fields (field (name "PUBLISHER") "Altium Limited"))
      (libsource (lib "NSC Logic Multiplexer") (part "74F151APC"))
    )
    (comp (ref "U1514")
      (value "74F151APC")
      (footprint "N16E")
      (description "8-Input Multiplexer")
      (fields (field (name "PUBLISHER") "Altium Limited"))
      (libsource (lib "NSC Logic Multiplexer") (part "74F151APC"))
    )
    (comp (ref "U1515")
      (value "74F151APC")
      (footprint "N16E")
      (description "8-Input Multiplexer")
      (fields (field (name "PUBLISHER") "Altium Limited"))
      (libsource (lib "NSC Logic Multiplexer") (part "74F151APC"))
    )
    (comp (ref "U28031")
      (value "ULN2803A")
      (footprint "DIP18")
      (description "Eight Darlington Array")
      (fields (field (name "PUBLISHER") "Altium Limited"))
      (libsource (lib "ST Interface Darlington Driver") (part "ULN2803A"))
    )
    (comp (ref "U28032")
      (value "ULN2803A")
      (footprint "DIP18")
      (description "Eight Darlington Array")
      (fields (field (name "PUBLISHER") "Altium Limited"))
      (libsource (lib "ST Interface Darlington Driver") (part "ULN2803A"))
    )
    (comp (ref "U28033")
      (value "ULN2803A")
      (footprint "DIP18")
      (description "Eight Darlington Array")
      (fields (field (name "PUBLISHER") "Altium Limited"))
      (libsource (lib "ST Interface Darlington Driver") (part "ULN2803A"))
    )
    (comp (ref "U28034")
      (value "ULN2803A")
      (footprint "DIP18")
      (description "Eight Darlington Array")
      (fields (field (name "PUBLISHER") "Altium Limited"))
      (libsource (lib "ST Interface Darlington Driver") (part "ULN2803A"))
    )
    (comp (ref "U28035")
      (value "ULN2803A")
      (footprint "DIP18")
      (description "Eight Darlington Array")
      (fields (field (name "PUBLISHER") "Altium Limited"))
      (libsource (lib "ST Interface Darlington Driver") (part "ULN2803A"))
    )
    (comp (ref "UART")
      (value "Header 3")
      (footprint "Device:HEADER3")
      (description "Header, 3-Pin")
      (fields (field (name "PUBLISHER") "Altium Limited"))
      (libsource (lib "") (part "Header 3_1"))
    )
    (comp (ref "Y1")
      (value "8MHz")
      (footprint "Device:Xtal12M")
      (description "Crystal Oscillator")
      (fields (field (name "PUBLISHER") "Altium Limited"))
      (libsource (lib "Miscellaneous Devices") (part "XTAL"))
    )
  )
  (nets
    (net (code "1") (name "+3V") (class "Default")
      (node (ref "C1") (pin "1") (pinfunction "1_1") (pintype "passive"))
      (node (ref "C2P") (pin "1") (pinfunction "1_1") (pintype "passive"))
      (node (ref "P1") (pin "2") (pinfunction "2_2") (pintype "passive"))
      (node (ref "POWER") (pin "3") (pinfunction "3_3") (pintype "passive"))
      (node (ref "R1") (pin "2") (pinfunction "2_2") (pintype "passive"))
      (node (ref "R1511") (pin "2") (pinfunction "2_2") (pintype "passive"))
      (node (ref "R1513") (pin "2") (pinfunction "2_2") (pintype "passive"))
      (node (ref "R1515") (pin "2") (pinfunction "2_2") (pintype "passive"))
      (node (ref "R1517") (pin "2") (pinfunction "2_2") (pintype "passive"))
      (node (ref "R1519") (pin "2") (pinfunction "2_2") (pintype "passive"))
      (node (ref "RD2") (pin "1") (pinfunction "1_1") (pintype "passive"))
      (node (ref "RP1") (pin "1") (pinfunction "1_1") (pintype "passive"))
      (node (ref "RRX") (pin "1") (pinfunction "1_1") (pintype "passive"))
      (node (ref "RTX") (pin "1") (pinfunction "1_1") (pintype "passive"))
      (node (ref "U1") (pin "20") (pinfunction "VDD_20") (pintype "power_in"))
    )
    (net (code "2") (name "/A") (class "Default")
      (node (ref "U081") (pin "11") (pinfunction "Y_11") (pintype "output"))
      (node (ref "U1511") (pin "11") (pinfunction "A_11") (pintype "input"))
      (node (ref "U1512") (pin "11") (pinfunction "A_11") (pintype "input"))
      (node (ref "U1513") (pin "11") (pinfunction "A_11") (pintype "input"))
      (node (ref "U1514") (pin "11") (pinfunction "A_11") (pintype "input"))
      (node (ref "U1515") (pin "11") (pinfunction "A_11") (pintype "input"))
    )
    (net (code "3") (name "/AP") (class "Default")
      (node (ref "U081") (pin "12") (pinfunction "A_12") (pintype "input"))
      (node (ref "U081") (pin "13") (pinfunction "B_13") (pintype "input"))
      (node (ref "U1") (pin "21") (pinfunction "RB0/INT0_21") (pintype "bidirectional"))
    )
    (net (code "4") (name "/B") (class "Default")
      (node (ref "U081") (pin "8") (pinfunction "Y_8") (pintype "output"))
      (node (ref "U1511") (pin "10") (pinfunction "B_10") (pintype "input"))
      (node (ref "U1512") (pin "10") (pinfunction "B_10") (pintype "input"))
      (node (ref "U1513") (pin "10") (pinfunction "B_10") (pintype "input"))
      (node (ref "U1514") (pin "10") (pinfunction "B_10") (pintype "input"))
      (node (ref "U1515") (pin "10") (pinfunction "B_10") (pintype "input"))
    )
    (net (code "5") (name "/BP") (class "Default")
      (node (ref "U081") (pin "10") (pinfunction "B_10") (pintype "input"))
      (node (ref "U081") (pin "9") (pinfunction "A_9") (pintype "input"))
      (node (ref "U1") (pin "22") (pinfunction "RB1/INT1_22") (pintype "bidirectional"))
    )
    (net (code "6") (name "/C") (class "Default")
      (node (ref "U081") (pin "6") (pinfunction "Y_6") (pintype "output"))
      (node (ref "U1511") (pin "9") (pinfunction "C_9") (pintype "input"))
      (node (ref "U1512") (pin "9") (pinfunction "C_9") (pintype "input"))
      (node (ref "U1513") (pin "9") (pinfunction "C_9") (pintype "input"))
      (node (ref "U1514") (pin "9") (pinfunction "C_9") (pintype "input"))
      (node (ref "U1515") (pin "9") (pinfunction "C_9") (pintype "input"))
    )
    (net (code "7") (name "/CP") (class "Default")
      (node (ref "U081") (pin "4") (pinfunction "A_4") (pintype "input"))
      (node (ref "U081") (pin "5") (pinfunction "B_5") (pintype "input"))
      (node (ref "U1") (pin "23") (pinfunction "RB2/INT2_23") (pintype "bidirectional"))
    )
    (net (code "8") (name "/IN1") (class "Default")
      (node (ref "R111") (pin "2") (pinfunction "2_2") (pintype "passive"))
      (node (ref "R128031") (pin "2") (pinfunction "2_2") (pintype "passive"))
    )
    (net (code "9") (name "/IN2") (class "Default")
      (node (ref "R2") (pin "2") (pinfunction "2_2") (pintype "passive"))
      (node (ref "R228031") (pin "2") (pinfunction "2_2") (pintype "passive"))
    )
    (net (code "10") (name "/IN3") (class "Default")
      (node (ref "R3") (pin "2") (pinfunction "2_2") (pintype "passive"))
      (node (ref "R328031") (pin "2") (pinfunction "2_2") (pintype "passive"))
    )
    (net (code "11") (name "/IN4") (class "Default")
      (node (ref "R4") (pin "2") (pinfunction "2_2") (pintype "passive"))
      (node (ref "R428031") (pin "2") (pinfunction "2_2") (pintype "passive"))
    )
    (net (code "12") (name "/IN5") (class "Default")
      (node (ref "R5") (pin "2") (pinfunction "2_2") (pintype "passive"))
      (node (ref "R528031") (pin "2") (pinfunction "2_2") (pintype "passive"))
    )
    (net (code "13") (name "/IN6") (class "Default")
      (node (ref "R6") (pin "2") (pinfunction "2_2") (pintype "passive"))
      (node (ref "R628031") (pin "2") (pinfunction "2_2") (pintype "passive"))
    )
    (net (code "14") (name "/IN7") (class "Default")
      (node (ref "R7") (pin "2") (pinfunction "2_2") (pintype "passive"))
      (node (ref "R728031") (pin "2") (pinfunction "2_2") (pintype "passive"))
    )
    (net (code "15") (name "/IN8") (class "Default")
      (node (ref "R8") (pin "2") (pinfunction "2_2") (pintype "passive"))
      (node (ref "R828031") (pin "2") (pinfunction "2_2") (pintype "passive"))
    )
    (net (code "16") (name "/IN9") (class "Default")
      (node (ref "R128032") (pin "2") (pinfunction "2_2") (pintype "passive"))
      (node (ref "R9") (pin "2") (pinfunction "2_2") (pintype "passive"))
    )
    (net (code "17") (name "/IN10") (class "Default")
      (node (ref "R10") (pin "2") (pinfunction "2_2") (pintype "passive"))
      (node (ref "R228032") (pin "2") (pinfunction "2_2") (pintype "passive"))
    )
    (net (code "18") (name "/IN11") (class "Default")
      (node (ref "R11") (pin "2") (pinfunction "2_2") (pintype "passive"))
      (node (ref "R328032") (pin "2") (pinfunction "2_2") (pintype "passive"))
    )
    (net (code "19") (name "/IN12") (class "Default")
      (node (ref "R12") (pin "2") (pinfunction "2_2") (pintype "passive"))
      (node (ref "R42802") (pin "2") (pinfunction "2_2") (pintype "passive"))
    )
    (net (code "20") (name "/IN13") (class "Default")
      (node (ref "R13") (pin "2") (pinfunction "2_2") (pintype "passive"))
      (node (ref "R528032") (pin "2") (pinfunction "2_2") (pintype "passive"))
    )
    (net (code "21") (name "/IN14") (class "Default")
      (node (ref "R14") (pin "2") (pinfunction "2_2") (pintype "passive"))
      (node (ref "R628032") (pin "2") (pinfunction "2_2") (pintype "passive"))
    )
    (net (code "22") (name "/IN15") (class "Default")
      (node (ref "R15") (pin "2") (pinfunction "2_2") (pintype "passive"))
      (node (ref "R728032") (pin "2") (pinfunction "2_2") (pintype "passive"))
    )
    (net (code "23") (name "/IN16") (class "Default")
      (node (ref "R16") (pin "2") (pinfunction "2_2") (pintype "passive"))
      (node (ref "R828032") (pin "2") (pinfunction "2_2") (pintype "passive"))
    )
    (net (code "24") (name "/IN17") (class "Default")
      (node (ref "R128033") (pin "2") (pinfunction "2_2") (pintype "passive"))
      (node (ref "R17") (pin "2") (pinfunction "2_2") (pintype "passive"))
    )
    (net (code "25") (name "/IN18") (class "Default")
      (node (ref "R18") (pin "2") (pinfunction "2_2") (pintype "passive"))
      (node (ref "R228033") (pin "2") (pinfunction "2_2") (pintype "passive"))
    )
    (net (code "26") (name "/IN19") (class "Default")
      (node (ref "R19") (pin "2") (pinfunction "2_2") (pintype "passive"))
      (node (ref "R328033") (pin "2") (pinfunction "2_2") (pintype "passive"))
    )
    (net (code "27") (name "/IN20") (class "Default")
      (node (ref "R20") (pin "2") (pinfunction "2_2") (pintype "passive"))
      (node (ref "R42803") (pin "2") (pinfunction "2_2") (pintype "passive"))
    )
    (net (code "28") (name "/IN21") (class "Default")
      (node (ref "R21") (pin "2") (pinfunction "2_2") (pintype "passive"))
      (node (ref "R528033") (pin "2") (pinfunction "2_2") (pintype "passive"))
    )
    (net (code "29") (name "/IN22") (class "Default")
      (node (ref "R22") (pin "2") (pinfunction "2_2") (pintype "passive"))
      (node (ref "R628033") (pin "2") (pinfunction "2_2") (pintype "passive"))
    )
    (net (code "30") (name "/IN23") (class "Default")
      (node (ref "R23") (pin "2") (pinfunction "2_2") (pintype "passive"))
      (node (ref "R728033") (pin "2") (pinfunction "2_2") (pintype "passive"))
    )
    (net (code "31") (name "/IN24") (class "Default")
      (node (ref "R24") (pin "2") (pinfunction "2_2") (pintype "passive"))
      (node (ref "R828033") (pin "2") (pinfunction "2_2") (pintype "passive"))
    )
    (net (code "32") (name "/IN25") (class "Default")
      (node (ref "R128034") (pin "2") (pinfunction "2_2") (pintype "passive"))
      (node (ref "R25") (pin "2") (pinfunction "2_2") (pintype "passive"))
    )
    (net (code "33") (name "/IN26") (class "Default")
      (node (ref "R228034") (pin "2") (pinfunction "2_2") (pintype "passive"))
      (node (ref "R26") (pin "2") (pinfunction "2_2") (pintype "passive"))
    )
    (net (code "34") (name "/IN27") (class "Default")
      (node (ref "R27") (pin "2") (pinfunction "2_2") (pintype "passive"))
      (node (ref "R328034") (pin "2") (pinfunction "2_2") (pintype "passive"))
    )
    (net (code "35") (name "/IN28") (class "Default")
      (node (ref "R28") (pin "2") (pinfunction "2_2") (pintype "passive"))
      (node (ref "R42804") (pin "2") (pinfunction "2_2") (pintype "passive"))
    )
    (net (code "36") (name "/IN29") (class "Default")
      (node (ref "R29") (pin "2") (pinfunction "2_2") (pintype "passive"))
      (node (ref "R528034") (pin "2") (pinfunction "2_2") (pintype "passive"))
    )
    (net (code "37") (name "/IN30") (class "Default")
      (node (ref "R30") (pin "2") (pinfunction "2_2") (pintype "passive"))
      (node (ref "R628034") (pin "2") (pinfunction "2_2") (pintype "passive"))
    )
    (net (code "38") (name "/IN31") (class "Default")
      (node (ref "R31") (pin "2") (pinfunction "2_2") (pintype "passive"))
      (node (ref "R728034") (pin "2") (pinfunction "2_2") (pintype "passive"))
    )
    (net (code "39") (name "/IN32") (class "Default")
      (node (ref "R32") (pin "2") (pinfunction "2_2") (pintype "passive"))
      (node (ref "R828034") (pin "2") (pinfunction "2_2") (pintype "passive"))
    )
    (net (code "40") (name "/IN33") (class "Default")
      (node (ref "R128035") (pin "2") (pinfunction "2_2") (pintype "passive"))
      (node (ref "R33") (pin "2") (pinfunction "2_2") (pintype "passive"))
    )
    (net (code "41") (name "/IN34") (class "Default")
      (node (ref "R228035") (pin "2") (pinfunction "2_2") (pintype "passive"))
      (node (ref "R34") (pin "2") (pinfunction "2_2") (pintype "passive"))
    )
    (net (code "42") (name "/IN35") (class "Default")
      (node (ref "R328035") (pin "2") (pinfunction "2_2") (pintype "passive"))
      (node (ref "R35") (pin "2") (pinfunction "2_2") (pintype "passive"))
    )
    (net (code "43") (name "/IN36") (class "Default")
      (node (ref "R36") (pin "2") (pinfunction "2_2") (pintype "passive"))
      (node (ref "R428035") (pin "2") (pinfunction "2_2") (pintype "passive"))
    )
    (net (code "44") (name "/IN37") (class "Default")
      (node (ref "R37") (pin "2") (pinfunction "2_2") (pintype "passive"))
      (node (ref "R528035") (pin "2") (pinfunction "2_2") (pintype "passive"))
    )
    (net (code "45") (name "/IN38") (class "Default")
      (node (ref "R38") (pin "2") (pinfunction "2_2") (pintype "passive"))
      (node (ref "R628035") (pin "2") (pinfunction "2_2") (pintype "passive"))
    )
    (net (code "46") (name "/IN39") (class "Default")
      (node (ref "R39") (pin "2") (pinfunction "2_2") (pintype "passive"))
      (node (ref "R728035") (pin "2") (pinfunction "2_2") (pintype "passive"))
    )
    (net (code "47") (name "/IN40") (class "Default")
      (node (ref "R40") (pin "2") (pinfunction "2_2") (pintype "passive"))
      (node (ref "R828035") (pin "2") (pinfunction "2_2") (pintype "passive"))
    )
    (net (code "48") (name "/LVP") (class "Default")
      (node (ref "P1") (pin "6") (pinfunction "6_6") (pintype "passive"))
    )
    (net (code "49") (name "/MCLR") (class "Default")
      (node (ref "P1") (pin "1") (pinfunction "1_1") (pintype "passive"))
      (node (ref "R1") (pin "1") (pinfunction "1_1") (pintype "passive"))
      (node (ref "U1") (pin "1") (pinfunction "~{MCLR}/VPP_1") (pintype "input"))
    )
    (net (code "50") (name "/PGC") (class "Default")
      (node (ref "P1") (pin "5") (pinfunction "5_5") (pintype "passive"))
      (node (ref "U1") (pin "27") (pinfunction "RB6/PGC_27") (pintype "bidirectional"))
    )
    (net (code "51") (name "/PGD") (class "Default")
      (node (ref "P1") (pin "4") (pinfunction "4_4") (pintype "passive"))
      (node (ref "U1") (pin "28") (pinfunction "RB7/PGD_28") (pintype "bidirectional"))
    )
    (net (code "52") (name "/RX") (class "Default")
      (node (ref "DRX") (pin "2") (pinfunction "K_2") (pintype "passive"))
      (node (ref "PUA1") (pin "2") (pinfunction "2_2") (pintype "passive"))
      (node (ref "PUA2") (pin "2") (pinfunction "2_2") (pintype "passive"))
      (node (ref "Rx21") (pin "1") (pinfunction "1_1") (pintype "passive"))
      (node (ref "Rx33") (pin "2") (pinfunction "2_2") (pintype "passive"))
      (node (ref "U1") (pin "18") (pinfunction "RC7/RX/DT_18") (pintype "bidirectional"))
    )
    (net (code "53") (name "/RX1") (class "Default")
      (node (ref "PUA1") (pin "1") (pinfunction "1_1") (pintype "passive"))
      (node (ref "Q1Rx") (pin "2") (pinfunction "C_2") (pintype "passive"))
      (node (ref "RD2") (pin "2") (pinfunction "2_2") (pintype "passive"))
    )
    (net (code "54") (name "/RX_D") (class "Default")
      (node (ref "PUA2") (pin "1") (pinfunction "1_1") (pintype "passive"))
      (node (ref "Rx5") (pin "1") (pinfunction "1_1") (pintype "passive"))
      (node (ref "UART") (pin "3") (pinfunction "3_3") (pintype "passive"))
    )
    (net (code "55") (name "/STB1") (class "Default")
      (node (ref "U081") (pin "3") (pinfunction "Y_3") (pintype "output"))
      (node (ref "U1511") (pin "7") (pinfunction "~{STB}_7") (pintype "input"))
    )
    (net (code "56") (name "/STB1P") (class "Default")
      (node (ref "U081") (pin "1") (pinfunction "A_1") (pintype "input"))
      (node (ref "U081") (pin "2") (pinfunction "B_2") (pintype "input"))
      (node (ref "U1") (pin "24") (pinfunction "RB3/CCP2_24") (pintype "bidirectional"))
    )
    (net (code "57") (name "/STB2") (class "Default")
      (node (ref "U082") (pin "11") (pinfunction "Y_11") (pintype "output"))
      (node (ref "U1512") (pin "7") (pinfunction "~{STB}_7") (pintype "input"))
    )
    (net (code "58") (name "/STB2P") (class "Default")
      (node (ref "U082") (pin "12") (pinfunction "A_12") (pintype "input"))
      (node (ref "U082") (pin "13") (pinfunction "B_13") (pintype "input"))
      (node (ref "U1") (pin "25") (pinfunction "RB4_25") (pintype "bidirectional"))
    )
    (net (code "59") (name "/STB3") (class "Default")
      (node (ref "U082") (pin "8") (pinfunction "Y_8") (pintype "output"))
      (node (ref "U1513") (pin "7") (pinfunction "~{STB}_7") (pintype "input"))
    )
    (net (code "60") (name "/STB3P") (class "Default")
      (node (ref "U082") (pin "10") (pinfunction "B_10") (pintype "input"))
      (node (ref "U082") (pin "9") (pinfunction "A_9") (pintype "input"))
      (node (ref "U1") (pin "26") (pinfunction "RB5/PGM_26") (pintype "bidirectional"))
    )
    (net (code "61") (name "/STB4") (class "Default")
      (node (ref "U082") (pin "6") (pinfunction "Y_6") (pintype "output"))
      (node (ref "U1514") (pin "7") (pinfunction "~{STB}_7") (pintype "input"))
    )
    (net (code "62") (name "/STB4P") (class "Default")
      (node (ref "U082") (pin "4") (pinfunction "A_4") (pintype "input"))
      (node (ref "U082") (pin "5") (pinfunction "B_5") (pintype "input"))
      (node (ref "U1") (pin "2") (pinfunction "RA0/AN0_2") (pintype "bidirectional"))
    )
    (net (code "63") (name "/STB5") (class "Default")
      (node (ref "U082") (pin "3") (pinfunction "Y_3") (pintype "output"))
      (node (ref "U1515") (pin "7") (pinfunction "~{STB}_7") (pintype "input"))
    )
    (net (code "64") (name "/STB5P") (class "Default")
      (node (ref "U082") (pin "1") (pinfunction "A_1") (pintype "input"))
      (node (ref "U082") (pin "2") (pinfunction "B_2") (pintype "input"))
      (node (ref "U1") (pin "3") (pinfunction "RA1/AN1_3") (pintype "bidirectional"))
    )
    (net (code "65") (name "/TH1") (class "Default")
      (node (ref "Q1") (pin "2") (pinfunction "C_2") (pintype "passive"))
      (node (ref "R1511") (pin "1") (pinfunction "1_1") (pintype "passive"))
      (node (ref "U1") (pin "11") (pinfunction "RC0/T1OSO/T1CKI_11") (pintype "bidirectional"))
    )
    (net (code "66") (name "/TH2") (class "Default")
      (node (ref "Q2") (pin "2") (pinfunction "C_2") (pintype "passive"))
      (node (ref "R1513") (pin "1") (pinfunction "1_1") (pintype "passive"))
      (node (ref "U1") (pin "12") (pinfunction "RC1/T1OSI/CCP2_12") (pintype "bidirectional"))
    )
    (net (code "67") (name "/TH3") (class "Default")
      (node (ref "Q3") (pin "2") (pinfunction "C_2") (pintype "passive"))
      (node (ref "R1515") (pin "1") (pinfunction "1_1") (pintype "passive"))
      (node (ref "U1") (pin "13") (pinfunction "RC2/CCP1_13") (pintype "bidirectional"))
    )
    (net (code "68") (name "/TH4") (class "Default")
      (node (ref "Q4") (pin "2") (pinfunction "C_2") (pintype "passive"))
      (node (ref "R1517") (pin "1") (pinfunction "1_1") (pintype "passive"))
      (node (ref "U1") (pin "14") (pinfunction "RC3/SCK/SCL_14") (pintype "bidirectional"))
    )
    (net (code "69") (name "/TH5") (class "Default")
      (node (ref "Q5") (pin "2") (pinfunction "C_2") (pintype "passive"))
      (node (ref "R1519") (pin "1") (pinfunction "1_1") (pintype "passive"))
      (node (ref "U1") (pin "15") (pinfunction "RC4/SDI/SDA_15") (pintype "bidirectional"))
    )
    (net (code "70") (name "/TX") (class "Default")
      (node (ref "DTX") (pin "2") (pinfunction "K_2") (pintype "passive"))
      (node (ref "U1") (pin "17") (pinfunction "RC6/TX/CK_17") (pintype "bidirectional"))
      (node (ref "UART") (pin "1") (pinfunction "1_1") (pintype "passive"))
    )
    (net (code "71") (name "GND") (class "Default")
      (node (ref "C081") (pin "2") (pinfunction "2_2") (pintype "passive"))
      (node (ref "C082") (pin "2") (pinfunction "2_2") (pintype "passive"))
      (node (ref "C1") (pin "2") (pinfunction "2_2") (pintype "passive"))
      (node (ref "C1511") (pin "2") (pinfunction "2_2") (pintype "passive"))
      (node (ref "C1512") (pin "2") (pinfunction "2_2") (pintype "passive"))
      (node (ref "C1513") (pin "2") (pinfunction "2_2") (pintype "passive"))
      (node (ref "C1514") (pin "2") (pinfunction "2_2") (pintype "passive"))
      (node (ref "C1515") (pin "2") (pinfunction "2_2") (pintype "passive"))
      (node (ref "C1P") (pin "2") (pinfunction "2_2") (pintype "passive"))
      (node (ref "C2") (pin "2") (pinfunction "2_2") (pintype "passive"))
      (node (ref "C2P") (pin "2") (pinfunction "2_2") (pintype "passive"))
      (node (ref "C3") (pin "2") (pinfunction "2_2") (pintype "passive"))
      (node (ref "DP1") (pin "2") (pinfunction "K_2") (pintype "passive"))
      (node (ref "DP2") (pin "2") (pinfunction "K_2") (pintype "passive"))
      (node (ref "P1") (pin "3") (pinfunction "3_3") (pintype "passive"))
      (node (ref "POWER") (pin "2") (pinfunction "2_2") (pintype "passive"))
      (node (ref "Q1") (pin "1") (pinfunction "E_1") (pintype "passive"))
      (node (ref "Q1Rx") (pin "1") (pinfunction "E_1") (pintype "passive"))
      (node (ref "Q2") (pin "1") (pinfunction "E_1") (pintype "passive"))
      (node (ref "Q3") (pin "1") (pinfunction "E_1") (pintype "passive"))
      (node (ref "Q4") (pin "1") (pinfunction "E_1") (pintype "passive"))
      (node (ref "Q5") (pin "1") (pinfunction "E_1") (pintype "passive"))
      (node (ref "R15121") (pin "2") (pinfunction "2_2") (pintype "passive"))
      (node (ref "R15122") (pin "2") (pinfunction "2_2") (pintype "passive"))
      (node (ref "R15123") (pin "2") (pinfunction "2_2") (pintype "passive"))
      (node (ref "R15124") (pin "2") (pinfunction "2_2") (pintype "passive"))
      (node (ref "R15125") (pin "2") (pinfunction "2_2") (pintype "passive"))
      (node (ref "RD6") (pin "1") (pinfunction "1_1") (pintype "passive"))
      (node (ref "Rx33") (pin "1") (pinfunction "1_1") (pintype "passive"))
      (node (ref "U081") (pin "7") (pinfunction "GND_7") (pintype "power_in"))
      (node (ref "U082") (pin "7") (pinfunction "GND_7") (pintype "power_in"))
      (node (ref "U1") (pin "19") (pinfunction "VSS_19") (pintype "power_in"))
      (node (ref "U1") (pin "8") (pinfunction "VSS_8") (pintype "power_in"))
      (node (ref "U1511") (pin "8") (pinfunction "GND_8") (pintype "power_in"))
      (node (ref "U1512") (pin "8") (pinfunction "GND_8") (pintype "power_in"))
      (node (ref "U1513") (pin "8") (pinfunction "GND_8") (pintype "power_in"))
      (node (ref "U1514") (pin "8") (pinfunction "GND_8") (pintype "power_in"))
      (node (ref "U1515") (pin "8") (pinfunction "GND_8") (pintype "power_in"))
      (node (ref "U28031") (pin "9") (pinfunction "GND_9") (pintype "power_in"))
      (node (ref "U28032") (pin "9") (pinfunction "GND_9") (pintype "power_in"))
      (node (ref "U28033") (pin "9") (pinfunction "GND_9") (pintype "power_in"))
      (node (ref "U28034") (pin "9") (pinfunction "GND_9") (pintype "power_in"))
      (node (ref "U28035") (pin "9") (pinfunction "GND_9") (pintype "power_in"))
      (node (ref "UART") (pin "2") (pinfunction "2_2") (pintype "passive"))
    )
    (net (code "72") (name "Net-(DP1-A)") (class "Default")
      (node (ref "DP1") (pin "1") (pinfunction "A_1") (pintype "passive"))
      (node (ref "RP1") (pin "2") (pinfunction "2_2") (pintype "passive"))
    )
    (net (code "73") (name "Net-(DP2-A)") (class "Default")
      (node (ref "DP2") (pin "1") (pinfunction "A_1") (pintype "passive"))
      (node (ref "Rp2") (pin "2") (pinfunction "2_2") (pintype "passive"))
    )
    (net (code "74") (name "Net-(DRX-A)") (class "Default")
      (node (ref "DRX") (pin "1") (pinfunction "A_1") (pintype "passive"))
      (node (ref "RRX") (pin "2") (pinfunction "2_2") (pintype "passive"))
    )
    (net (code "75") (name "Net-(DTX-A)") (class "Default")
      (node (ref "DTX") (pin "1") (pinfunction "A_1") (pintype "passive"))
      (node (ref "RTX") (pin "2") (pinfunction "2_2") (pintype "passive"))
    )
    (net (code "76") (name "Net-(PI1-1)") (class "Default")
      (node (ref "PI1") (pin "2") (pinfunction "1_2") (pintype "passive"))
      (node (ref "R2") (pin "1") (pinfunction "1_1") (pintype "passive"))
    )
    (net (code "77") (name "Net-(PI1-2)") (class "Default")
      (node (ref "PI1") (pin "1") (pinfunction "2_1") (pintype "passive"))
      (node (ref "R111") (pin "1") (pinfunction "1_1") (pintype "passive"))
    )
    (net (code "78") (name "Net-(PI2-1)") (class "Default")
      (node (ref "PI2") (pin "2") (pinfunction "1_2") (pintype "passive"))
      (node (ref "R4") (pin "1") (pinfunction "1_1") (pintype "passive"))
    )
    (net (code "79") (name "Net-(PI2-2)") (class "Default")
      (node (ref "PI2") (pin "1") (pinfunction "2_1") (pintype "passive"))
      (node (ref "R3") (pin "1") (pinfunction "1_1") (pintype "passive"))
    )
    (net (code "80") (name "Net-(PI3-1)") (class "Default")
      (node (ref "PI3") (pin "2") (pinfunction "1_2") (pintype "passive"))
      (node (ref "R6") (pin "1") (pinfunction "1_1") (pintype "passive"))
    )
    (net (code "81") (name "Net-(PI3-2)") (class "Default")
      (node (ref "PI3") (pin "1") (pinfunction "2_1") (pintype "passive"))
      (node (ref "R5") (pin "1") (pinfunction "1_1") (pintype "passive"))
    )
    (net (code "82") (name "Net-(PI4-1)") (class "Default")
      (node (ref "PI4") (pin "2") (pinfunction "1_2") (pintype "passive"))
      (node (ref "R8") (pin "1") (pinfunction "1_1") (pintype "passive"))
    )
    (net (code "83") (name "Net-(PI4-2)") (class "Default")
      (node (ref "PI4") (pin "1") (pinfunction "2_1") (pintype "passive"))
      (node (ref "R7") (pin "1") (pinfunction "1_1") (pintype "passive"))
    )
    (net (code "84") (name "Net-(PI5-1)") (class "Default")
      (node (ref "PI5") (pin "2") (pinfunction "1_2") (pintype "passive"))
      (node (ref "R10") (pin "1") (pinfunction "1_1") (pintype "passive"))
    )
    (net (code "85") (name "Net-(PI5-2)") (class "Default")
      (node (ref "PI5") (pin "1") (pinfunction "2_1") (pintype "passive"))
      (node (ref "R9") (pin "1") (pinfunction "1_1") (pintype "passive"))
    )
    (net (code "86") (name "Net-(PI6-1)") (class "Default")
      (node (ref "PI6") (pin "2") (pinfunction "1_2") (pintype "passive"))
      (node (ref "R12") (pin "1") (pinfunction "1_1") (pintype "passive"))
    )
    (net (code "87") (name "Net-(PI6-2)") (class "Default")
      (node (ref "PI6") (pin "1") (pinfunction "2_1") (pintype "passive"))
      (node (ref "R11") (pin "1") (pinfunction "1_1") (pintype "passive"))
    )
    (net (code "88") (name "Net-(PI7-1)") (class "Default")
      (node (ref "PI7") (pin "2") (pinfunction "1_2") (pintype "passive"))
      (node (ref "R14") (pin "1") (pinfunction "1_1") (pintype "passive"))
    )
    (net (code "89") (name "Net-(PI7-2)") (class "Default")
      (node (ref "PI7") (pin "1") (pinfunction "2_1") (pintype "passive"))
      (node (ref "R13") (pin "1") (pinfunction "1_1") (pintype "passive"))
    )
    (net (code "90") (name "Net-(PI8-1)") (class "Default")
      (node (ref "PI8") (pin "2") (pinfunction "1_2") (pintype "passive"))
      (node (ref "R16") (pin "1") (pinfunction "1_1") (pintype "passive"))
    )
    (net (code "91") (name "Net-(PI8-2)") (class "Default")
      (node (ref "PI8") (pin "1") (pinfunction "2_1") (pintype "passive"))
      (node (ref "R15") (pin "1") (pinfunction "1_1") (pintype "passive"))
    )
    (net (code "92") (name "Net-(PI9-1)") (class "Default")
      (node (ref "PI9") (pin "2") (pinfunction "1_2") (pintype "passive"))
      (node (ref "R18") (pin "1") (pinfunction "1_1") (pintype "passive"))
    )
    (net (code "93") (name "Net-(PI9-2)") (class "Default")
      (node (ref "PI9") (pin "1") (pinfunction "2_1") (pintype "passive"))
      (node (ref "R17") (pin "1") (pinfunction "1_1") (pintype "passive"))
    )
    (net (code "94") (name "Net-(PI10-1)") (class "Default")
      (node (ref "PI10") (pin "2") (pinfunction "1_2") (pintype "passive"))
      (node (ref "R20") (pin "1") (pinfunction "1_1") (pintype "passive"))
    )
    (net (code "95") (name "Net-(PI10-2)") (class "Default")
      (node (ref "PI10") (pin "1") (pinfunction "2_1") (pintype "passive"))
      (node (ref "R19") (pin "1") (pinfunction "1_1") (pintype "passive"))
    )
    (net (code "96") (name "Net-(PI11-1)") (class "Default")
      (node (ref "PI11") (pin "2") (pinfunction "1_2") (pintype "passive"))
      (node (ref "R22") (pin "1") (pinfunction "1_1") (pintype "passive"))
    )
    (net (code "97") (name "Net-(PI11-2)") (class "Default")
      (node (ref "PI11") (pin "1") (pinfunction "2_1") (pintype "passive"))
      (node (ref "R21") (pin "1") (pinfunction "1_1") (pintype "passive"))
    )
    (net (code "98") (name "Net-(PI12-1)") (class "Default")
      (node (ref "PI12") (pin "2") (pinfunction "1_2") (pintype "passive"))
      (node (ref "R24") (pin "1") (pinfunction "1_1") (pintype "passive"))
    )
    (net (code "99") (name "Net-(PI12-2)") (class "Default")
      (node (ref "PI12") (pin "1") (pinfunction "2_1") (pintype "passive"))
      (node (ref "R23") (pin "1") (pinfunction "1_1") (pintype "passive"))
    )
    (net (code "100") (name "Net-(PI13-1)") (class "Default")
      (node (ref "PI13") (pin "2") (pinfunction "1_2") (pintype "passive"))
      (node (ref "R26") (pin "1") (pinfunction "1_1") (pintype "passive"))
    )
    (net (code "101") (name "Net-(PI13-2)") (class "Default")
      (node (ref "PI13") (pin "1") (pinfunction "2_1") (pintype "passive"))
      (node (ref "R25") (pin "1") (pinfunction "1_1") (pintype "passive"))
    )
    (net (code "102") (name "Net-(PI14-1)") (class "Default")
      (node (ref "PI14") (pin "2") (pinfunction "1_2") (pintype "passive"))
      (node (ref "R28") (pin "1") (pinfunction "1_1") (pintype "passive"))
    )
    (net (code "103") (name "Net-(PI14-2)") (class "Default")
      (node (ref "PI14") (pin "1") (pinfunction "2_1") (pintype "passive"))
      (node (ref "R27") (pin "1") (pinfunction "1_1") (pintype "passive"))
    )
    (net (code "104") (name "Net-(PI15-1)") (class "Default")
      (node (ref "PI15") (pin "2") (pinfunction "1_2") (pintype "passive"))
      (node (ref "R30") (pin "1") (pinfunction "1_1") (pintype "passive"))
    )
    (net (code "105") (name "Net-(PI15-2)") (class "Default")
      (node (ref "PI15") (pin "1") (pinfunction "2_1") (pintype "passive"))
      (node (ref "R29") (pin "1") (pinfunction "1_1") (pintype "passive"))
    )
    (net (code "106") (name "Net-(PI16-1)") (class "Default")
      (node (ref "PI16") (pin "2") (pinfunction "1_2") (pintype "passive"))
      (node (ref "R32") (pin "1") (pinfunction "1_1") (pintype "passive"))
    )
    (net (code "107") (name "Net-(PI16-2)") (class "Default")
      (node (ref "PI16") (pin "1") (pinfunction "2_1") (pintype "passive"))
      (node (ref "R31") (pin "1") (pinfunction "1_1") (pintype "passive"))
    )
    (net (code "108") (name "Net-(PI17-1)") (class "Default")
      (node (ref "PI17") (pin "2") (pinfunction "1_2") (pintype "passive"))
      (node (ref "R34") (pin "1") (pinfunction "1_1") (pintype "passive"))
    )
    (net (code "109") (name "Net-(PI17-2)") (class "Default")
      (node (ref "PI17") (pin "1") (pinfunction "2_1") (pintype "passive"))
      (node (ref "R33") (pin "1") (pinfunction "1_1") (pintype "passive"))
    )
    (net (code "110") (name "Net-(PI18-1)") (class "Default")
      (node (ref "PI18") (pin "2") (pinfunction "1_2") (pintype "passive"))
      (node (ref "R36") (pin "1") (pinfunction "1_1") (pintype "passive"))
    )
    (net (code "111") (name "Net-(PI18-2)") (class "Default")
      (node (ref "PI18") (pin "1") (pinfunction "2_1") (pintype "passive"))
      (node (ref "R35") (pin "1") (pinfunction "1_1") (pintype "passive"))
    )
    (net (code "112") (name "Net-(PI19-1)") (class "Default")
      (node (ref "PI19") (pin "2") (pinfunction "1_2") (pintype "passive"))
      (node (ref "R38") (pin "1") (pinfunction "1_1") (pintype "passive"))
    )
    (net (code "113") (name "Net-(PI19-2)") (class "Default")
      (node (ref "PI19") (pin "1") (pinfunction "2_1") (pintype "passive"))
      (node (ref "R37") (pin "1") (pinfunction "1_1") (pintype "passive"))
    )
    (net (code "114") (name "Net-(PI20-1)") (class "Default")
      (node (ref "PI20") (pin "2") (pinfunction "1_2") (pintype "passive"))
      (node (ref "R40") (pin "1") (pinfunction "1_1") (pintype "passive"))
    )
    (net (code "115") (name "Net-(PI20-2)") (class "Default")
      (node (ref "PI20") (pin "1") (pinfunction "2_1") (pintype "passive"))
      (node (ref "R39") (pin "1") (pinfunction "1_1") (pintype "passive"))
    )
    (net (code "116") (name "Net-(Q1-B)") (class "Default")
      (node (ref "Q1") (pin "3") (pinfunction "B_3") (pintype "passive"))
      (node (ref "R1512") (pin "1") (pinfunction "1_1") (pintype "passive"))
      (node (ref "R15121") (pin "1") (pinfunction "1_1") (pintype "passive"))
    )
    (net (code "117") (name "Net-(Q1Rx-B)") (class "Default")
      (node (ref "Q1Rx") (pin "3") (pinfunction "B_3") (pintype "passive"))
      (node (ref "RD6") (pin "2") (pinfunction "2_2") (pintype "passive"))
      (node (ref "Rx5") (pin "2") (pinfunction "2_2") (pintype "passive"))
    )
    (net (code "118") (name "Net-(Q2-B)") (class "Default")
      (node (ref "Q2") (pin "3") (pinfunction "B_3") (pintype "passive"))
      (node (ref "R15122") (pin "1") (pinfunction "1_1") (pintype "passive"))
      (node (ref "R1514") (pin "1") (pinfunction "1_1") (pintype "passive"))
    )
    (net (code "119") (name "Net-(Q3-B)") (class "Default")
      (node (ref "Q3") (pin "3") (pinfunction "B_3") (pintype "passive"))
      (node (ref "R15123") (pin "1") (pinfunction "1_1") (pintype "passive"))
      (node (ref "R1516") (pin "1") (pinfunction "1_1") (pintype "passive"))
    )
    (net (code "120") (name "Net-(Q4-B)") (class "Default")
      (node (ref "Q4") (pin "3") (pinfunction "B_3") (pintype "passive"))
      (node (ref "R15124") (pin "1") (pinfunction "1_1") (pintype "passive"))
      (node (ref "R1518") (pin "1") (pinfunction "1_1") (pintype "passive"))
    )
    (net (code "121") (name "Net-(Q5-B)") (class "Default")
      (node (ref "Q5") (pin "3") (pinfunction "B_3") (pintype "passive"))
      (node (ref "R15110") (pin "1") (pinfunction "1_1") (pintype "passive"))
      (node (ref "R15125") (pin "1") (pinfunction "1_1") (pintype "passive"))
    )
    (net (code "122") (name "Net-(U1-OSC1{slash}CLKI)") (class "Default")
      (node (ref "C3") (pin "1") (pinfunction "1_1") (pintype "passive"))
      (node (ref "U1") (pin "9") (pinfunction "OSC1/CLKI_9") (pintype "input"))
      (node (ref "Y1") (pin "1") (pinfunction "OSC1_1") (pintype "passive"))
    )
    (net (code "123") (name "Net-(U1-OSC2{slash}CLKO{slash}RA6)") (class "Default")
      (node (ref "C2") (pin "1") (pinfunction "1_1") (pintype "passive"))
      (node (ref "U1") (pin "10") (pinfunction "OSC2/CLKO/RA6_10") (pintype "bidirectional"))
      (node (ref "Y1") (pin "2") (pinfunction "OSC2_2") (pintype "passive"))
    )
    (net (code "124") (name "Net-(U1511-D0)") (class "Default")
      (node (ref "P031") (pin "1") (pinfunction "1_1") (pintype "passive"))
      (node (ref "U1511") (pin "4") (pinfunction "D0_4") (pintype "input"))
      (node (ref "U28031") (pin "18") (pinfunction "OUT1_18") (pintype "open_collector"))
    )
    (net (code "125") (name "Net-(U1511-D1)") (class "Default")
      (node (ref "P031") (pin "2") (pinfunction "2_2") (pintype "passive"))
      (node (ref "U1511") (pin "3") (pinfunction "D1_3") (pintype "input"))
      (node (ref "U28031") (pin "17") (pinfunction "OUT2_17") (pintype "open_collector"))
    )
    (net (code "126") (name "Net-(U1511-D2)") (class "Default")
      (node (ref "P031") (pin "3") (pinfunction "3_3") (pintype "passive"))
      (node (ref "U1511") (pin "2") (pinfunction "D2_2") (pintype "input"))
      (node (ref "U28031") (pin "16") (pinfunction "OUT3_16") (pintype "open_collector"))
    )
    (net (code "127") (name "Net-(U1511-D3)") (class "Default")
      (node (ref "P031") (pin "4") (pinfunction "4_4") (pintype "passive"))
      (node (ref "U1511") (pin "1") (pinfunction "D3_1") (pintype "input"))
      (node (ref "U28031") (pin "15") (pinfunction "OUT4_15") (pintype "open_collector"))
    )
    (net (code "128") (name "Net-(U1511-D4)") (class "Default")
      (node (ref "P031") (pin "5") (pinfunction "5_5") (pintype "passive"))
      (node (ref "U1511") (pin "15") (pinfunction "D4_15") (pintype "input"))
      (node (ref "U28031") (pin "14") (pinfunction "OUT5_14") (pintype "open_collector"))
    )
    (net (code "129") (name "Net-(U1511-D5)") (class "Default")
      (node (ref "P031") (pin "6") (pinfunction "6_6") (pintype "passive"))
      (node (ref "U1511") (pin "14") (pinfunction "D5_14") (pintype "input"))
      (node (ref "U28031") (pin "13") (pinfunction "OUT6_13") (pintype "open_collector"))
    )
    (net (code "130") (name "Net-(U1511-D6)") (class "Default")
      (node (ref "P031") (pin "7") (pinfunction "7_7") (pintype "passive"))
      (node (ref "U1511") (pin "13") (pinfunction "D6_13") (pintype "input"))
      (node (ref "U28031") (pin "12") (pinfunction "OUT7_12") (pintype "open_collector"))
    )
    (net (code "131") (name "Net-(U1511-D7)") (class "Default")
      (node (ref "P031") (pin "8") (pinfunction "8_8") (pintype "passive"))
      (node (ref "U1511") (pin "12") (pinfunction "D7_12") (pintype "input"))
      (node (ref "U28031") (pin "11") (pinfunction "OUT8_11") (pintype "open_collector"))
    )
    (net (code "132") (name "Net-(U1511-Y)") (class "Default")
      (node (ref "R1512") (pin "2") (pinfunction "2_2") (pintype "passive"))
      (node (ref "U1511") (pin "5") (pinfunction "Y_5") (pintype "output"))
    )
    (net (code "133") (name "Net-(U1512-D0)") (class "Default")
      (node (ref "P032") (pin "1") (pinfunction "1_1") (pintype "passive"))
      (node (ref "U1512") (pin "4") (pinfunction "D0_4") (pintype "input"))
      (node (ref "U28032") (pin "18") (pinfunction "OUT1_18") (pintype "open_collector"))
    )
    (net (code "134") (name "Net-(U1512-D1)") (class "Default")
      (node (ref "P032") (pin "2") (pinfunction "2_2") (pintype "passive"))
      (node (ref "U1512") (pin "3") (pinfunction "D1_3") (pintype "input"))
      (node (ref "U28032") (pin "17") (pinfunction "OUT2_17") (pintype "open_collector"))
    )
    (net (code "135") (name "Net-(U1512-D2)") (class "Default")
      (node (ref "P032") (pin "3") (pinfunction "3_3") (pintype "passive"))
      (node (ref "U1512") (pin "2") (pinfunction "D2_2") (pintype "input"))
      (node (ref "U28032") (pin "16") (pinfunction "OUT3_16") (pintype "open_collector"))
    )
    (net (code "136") (name "Net-(U1512-D3)") (class "Default")
      (node (ref "P032") (pin "4") (pinfunction "4_4") (pintype "passive"))
      (node (ref "U1512") (pin "1") (pinfunction "D3_1") (pintype "input"))
      (node (ref "U28032") (pin "15") (pinfunction "OUT4_15") (pintype "open_collector"))
    )
    (net (code "137") (name "Net-(U1512-D4)") (class "Default")
      (node (ref "P032") (pin "5") (pinfunction "5_5") (pintype "passive"))
      (node (ref "U1512") (pin "15") (pinfunction "D4_15") (pintype "input"))
      (node (ref "U28032") (pin "14") (pinfunction "OUT5_14") (pintype "open_collector"))
    )
    (net (code "138") (name "Net-(U1512-D5)") (class "Default")
      (node (ref "P032") (pin "6") (pinfunction "6_6") (pintype "passive"))
      (node (ref "U1512") (pin "14") (pinfunction "D5_14") (pintype "input"))
      (node (ref "U28032") (pin "13") (pinfunction "OUT6_13") (pintype "open_collector"))
    )
    (net (code "139") (name "Net-(U1512-D6)") (class "Default")
      (node (ref "P032") (pin "7") (pinfunction "7_7") (pintype "passive"))
      (node (ref "U1512") (pin "13") (pinfunction "D6_13") (pintype "input"))
      (node (ref "U28032") (pin "12") (pinfunction "OUT7_12") (pintype "open_collector"))
    )
    (net (code "140") (name "Net-(U1512-D7)") (class "Default")
      (node (ref "P032") (pin "8") (pinfunction "8_8") (pintype "passive"))
      (node (ref "U1512") (pin "12") (pinfunction "D7_12") (pintype "input"))
      (node (ref "U28032") (pin "11") (pinfunction "OUT8_11") (pintype "open_collector"))
    )
    (net (code "141") (name "Net-(U1512-Y)") (class "Default")
      (node (ref "R1514") (pin "2") (pinfunction "2_2") (pintype "passive"))
      (node (ref "U1512") (pin "5") (pinfunction "Y_5") (pintype "output"))
    )
    (net (code "142") (name "Net-(U1513-D0)") (class "Default")
      (node (ref "P033") (pin "1") (pinfunction "1_1") (pintype "passive"))
      (node (ref "U1513") (pin "4") (pinfunction "D0_4") (pintype "input"))
      (node (ref "U28033") (pin "18") (pinfunction "OUT1_18") (pintype "open_collector"))
    )
    (net (code "143") (name "Net-(U1513-D1)") (class "Default")
      (node (ref "P033") (pin "2") (pinfunction "2_2") (pintype "passive"))
      (node (ref "U1513") (pin "3") (pinfunction "D1_3") (pintype "input"))
      (node (ref "U28033") (pin "17") (pinfunction "OUT2_17") (pintype "open_collector"))
    )
    (net (code "144") (name "Net-(U1513-D2)") (class "Default")
      (node (ref "P033") (pin "3") (pinfunction "3_3") (pintype "passive"))
      (node (ref "U1513") (pin "2") (pinfunction "D2_2") (pintype "input"))
      (node (ref "U28033") (pin "16") (pinfunction "OUT3_16") (pintype "open_collector"))
    )
    (net (code "145") (name "Net-(U1513-D3)") (class "Default")
      (node (ref "P033") (pin "4") (pinfunction "4_4") (pintype "passive"))
      (node (ref "U1513") (pin "1") (pinfunction "D3_1") (pintype "input"))
      (node (ref "U28033") (pin "15") (pinfunction "OUT4_15") (pintype "open_collector"))
    )
    (net (code "146") (name "Net-(U1513-D4)") (class "Default")
      (node (ref "P033") (pin "5") (pinfunction "5_5") (pintype "passive"))
      (node (ref "U1513") (pin "15") (pinfunction "D4_15") (pintype "input"))
      (node (ref "U28033") (pin "14") (pinfunction "OUT5_14") (pintype "open_collector"))
    )
    (net (code "147") (name "Net-(U1513-D5)") (class "Default")
      (node (ref "P033") (pin "6") (pinfunction "6_6") (pintype "passive"))
      (node (ref "U1513") (pin "14") (pinfunction "D5_14") (pintype "input"))
      (node (ref "U28033") (pin "13") (pinfunction "OUT6_13") (pintype "open_collector"))
    )
    (net (code "148") (name "Net-(U1513-D6)") (class "Default")
      (node (ref "P033") (pin "7") (pinfunction "7_7") (pintype "passive"))
      (node (ref "U1513") (pin "13") (pinfunction "D6_13") (pintype "input"))
      (node (ref "U28033") (pin "12") (pinfunction "OUT7_12") (pintype "open_collector"))
    )
    (net (code "149") (name "Net-(U1513-D7)") (class "Default")
      (node (ref "P033") (pin "8") (pinfunction "8_8") (pintype "passive"))
      (node (ref "U1513") (pin "12") (pinfunction "D7_12") (pintype "input"))
      (node (ref "U28033") (pin "11") (pinfunction "OUT8_11") (pintype "open_collector"))
    )
    (net (code "150") (name "Net-(U1513-Y)") (class "Default")
      (node (ref "R1516") (pin "2") (pinfunction "2_2") (pintype "passive"))
      (node (ref "U1513") (pin "5") (pinfunction "Y_5") (pintype "output"))
    )
    (net (code "151") (name "Net-(U1514-D0)") (class "Default")
      (node (ref "P034") (pin "1") (pinfunction "1_1") (pintype "passive"))
      (node (ref "U1514") (pin "4") (pinfunction "D0_4") (pintype "input"))
      (node (ref "U28034") (pin "18") (pinfunction "OUT1_18") (pintype "open_collector"))
    )
    (net (code "152") (name "Net-(U1514-D1)") (class "Default")
      (node (ref "P034") (pin "2") (pinfunction "2_2") (pintype "passive"))
      (node (ref "U1514") (pin "3") (pinfunction "D1_3") (pintype "input"))
      (node (ref "U28034") (pin "17") (pinfunction "OUT2_17") (pintype "open_collector"))
    )
    (net (code "153") (name "Net-(U1514-D2)") (class "Default")
      (node (ref "P034") (pin "3") (pinfunction "3_3") (pintype "passive"))
      (node (ref "U1514") (pin "2") (pinfunction "D2_2") (pintype "input"))
      (node (ref "U28034") (pin "16") (pinfunction "OUT3_16") (pintype "open_collector"))
    )
    (net (code "154") (name "Net-(U1514-D3)") (class "Default")
      (node (ref "P034") (pin "4") (pinfunction "4_4") (pintype "passive"))
      (node (ref "U1514") (pin "1") (pinfunction "D3_1") (pintype "input"))
      (node (ref "U28034") (pin "15") (pinfunction "OUT4_15") (pintype "open_collector"))
    )
    (net (code "155") (name "Net-(U1514-D4)") (class "Default")
      (node (ref "P034") (pin "5") (pinfunction "5_5") (pintype "passive"))
      (node (ref "U1514") (pin "15") (pinfunction "D4_15") (pintype "input"))
      (node (ref "U28034") (pin "14") (pinfunction "OUT5_14") (pintype "open_collector"))
    )
    (net (code "156") (name "Net-(U1514-D5)") (class "Default")
      (node (ref "P034") (pin "6") (pinfunction "6_6") (pintype "passive"))
      (node (ref "U1514") (pin "14") (pinfunction "D5_14") (pintype "input"))
      (node (ref "U28034") (pin "13") (pinfunction "OUT6_13") (pintype "open_collector"))
    )
    (net (code "157") (name "Net-(U1514-D6)") (class "Default")
      (node (ref "P034") (pin "7") (pinfunction "7_7") (pintype "passive"))
      (node (ref "U1514") (pin "13") (pinfunction "D6_13") (pintype "input"))
      (node (ref "U28034") (pin "12") (pinfunction "OUT7_12") (pintype "open_collector"))
    )
    (net (code "158") (name "Net-(U1514-D7)") (class "Default")
      (node (ref "P034") (pin "8") (pinfunction "8_8") (pintype "passive"))
      (node (ref "U1514") (pin "12") (pinfunction "D7_12") (pintype "input"))
      (node (ref "U28034") (pin "11") (pinfunction "OUT8_11") (pintype "open_collector"))
    )
    (net (code "159") (name "Net-(U1514-Y)") (class "Default")
      (node (ref "R1518") (pin "2") (pinfunction "2_2") (pintype "passive"))
      (node (ref "U1514") (pin "5") (pinfunction "Y_5") (pintype "output"))
    )
    (net (code "160") (name "Net-(U1515-D0)") (class "Default")
      (node (ref "P035") (pin "1") (pinfunction "1_1") (pintype "passive"))
      (node (ref "U1515") (pin "4") (pinfunction "D0_4") (pintype "input"))
      (node (ref "U28035") (pin "18") (pinfunction "OUT1_18") (pintype "open_collector"))
    )
    (net (code "161") (name "Net-(U1515-D1)") (class "Default")
      (node (ref "P035") (pin "2") (pinfunction "2_2") (pintype "passive"))
      (node (ref "U1515") (pin "3") (pinfunction "D1_3") (pintype "input"))
      (node (ref "U28035") (pin "17") (pinfunction "OUT2_17") (pintype "open_collector"))
    )
    (net (code "162") (name "Net-(U1515-D2)") (class "Default")
      (node (ref "P035") (pin "3") (pinfunction "3_3") (pintype "passive"))
      (node (ref "U1515") (pin "2") (pinfunction "D2_2") (pintype "input"))
      (node (ref "U28035") (pin "16") (pinfunction "OUT3_16") (pintype "open_collector"))
    )
    (net (code "163") (name "Net-(U1515-D3)") (class "Default")
      (node (ref "P035") (pin "4") (pinfunction "4_4") (pintype "passive"))
      (node (ref "U1515") (pin "1") (pinfunction "D3_1") (pintype "input"))
      (node (ref "U28035") (pin "15") (pinfunction "OUT4_15") (pintype "open_collector"))
    )
    (net (code "164") (name "Net-(U1515-D4)") (class "Default")
      (node (ref "P035") (pin "5") (pinfunction "5_5") (pintype "passive"))
      (node (ref "U1515") (pin "15") (pinfunction "D4_15") (pintype "input"))
      (node (ref "U28035") (pin "14") (pinfunction "OUT5_14") (pintype "open_collector"))
    )
    (net (code "165") (name "Net-(U1515-D5)") (class "Default")
      (node (ref "P035") (pin "6") (pinfunction "6_6") (pintype "passive"))
      (node (ref "U1515") (pin "14") (pinfunction "D5_14") (pintype "input"))
      (node (ref "U28035") (pin "13") (pinfunction "OUT6_13") (pintype "open_collector"))
    )
    (net (code "166") (name "Net-(U1515-D6)") (class "Default")
      (node (ref "P035") (pin "7") (pinfunction "7_7") (pintype "passive"))
      (node (ref "U1515") (pin "13") (pinfunction "D6_13") (pintype "input"))
      (node (ref "U28035") (pin "12") (pinfunction "OUT7_12") (pintype "open_collector"))
    )
    (net (code "167") (name "Net-(U1515-D7)") (class "Default")
      (node (ref "P035") (pin "8") (pinfunction "8_8") (pintype "passive"))
      (node (ref "U1515") (pin "12") (pinfunction "D7_12") (pintype "input"))
      (node (ref "U28035") (pin "11") (pinfunction "OUT8_11") (pintype "open_collector"))
    )
    (net (code "168") (name "Net-(U1515-Y)") (class "Default")
      (node (ref "R15110") (pin "2") (pinfunction "2_2") (pintype "passive"))
      (node (ref "U1515") (pin "5") (pinfunction "Y_5") (pintype "output"))
    )
    (net (code "169") (name "Net-(U28031-IN1)") (class "Default")
      (node (ref "R128031") (pin "1") (pinfunction "1_1") (pintype "passive"))
      (node (ref "U28031") (pin "1") (pinfunction "IN1_1") (pintype "input"))
    )
    (net (code "170") (name "Net-(U28031-IN2)") (class "Default")
      (node (ref "R228031") (pin "1") (pinfunction "1_1") (pintype "passive"))
      (node (ref "U28031") (pin "2") (pinfunction "IN2_2") (pintype "input"))
    )
    (net (code "171") (name "Net-(U28031-IN3)") (class "Default")
      (node (ref "R328031") (pin "1") (pinfunction "1_1") (pintype "passive"))
      (node (ref "U28031") (pin "3") (pinfunction "IN3_3") (pintype "input"))
    )
    (net (code "172") (name "Net-(U28031-IN4)") (class "Default")
      (node (ref "R428031") (pin "1") (pinfunction "1_1") (pintype "passive"))
      (node (ref "U28031") (pin "4") (pinfunction "IN4_4") (pintype "input"))
    )
    (net (code "173") (name "Net-(U28031-IN5)") (class "Default")
      (node (ref "R528031") (pin "1") (pinfunction "1_1") (pintype "passive"))
      (node (ref "U28031") (pin "5") (pinfunction "IN5_5") (pintype "input"))
    )
    (net (code "174") (name "Net-(U28031-IN6)") (class "Default")
      (node (ref "R628031") (pin "1") (pinfunction "1_1") (pintype "passive"))
      (node (ref "U28031") (pin "6") (pinfunction "IN6_6") (pintype "input"))
    )
    (net (code "175") (name "Net-(U28031-IN7)") (class "Default")
      (node (ref "R728031") (pin "1") (pinfunction "1_1") (pintype "passive"))
      (node (ref "U28031") (pin "7") (pinfunction "IN7_7") (pintype "input"))
    )
    (net (code "176") (name "Net-(U28031-IN8)") (class "Default")
      (node (ref "R828031") (pin "1") (pinfunction "1_1") (pintype "passive"))
      (node (ref "U28031") (pin "8") (pinfunction "IN8_8") (pintype "input"))
    )
    (net (code "177") (name "Net-(U28032-IN1)") (class "Default")
      (node (ref "R128032") (pin "1") (pinfunction "1_1") (pintype "passive"))
      (node (ref "U28032") (pin "1") (pinfunction "IN1_1") (pintype "input"))
    )
    (net (code "178") (name "Net-(U28032-IN2)") (class "Default")
      (node (ref "R228032") (pin "1") (pinfunction "1_1") (pintype "passive"))
      (node (ref "U28032") (pin "2") (pinfunction "IN2_2") (pintype "input"))
    )
    (net (code "179") (name "Net-(U28032-IN3)") (class "Default")
      (node (ref "R328032") (pin "1") (pinfunction "1_1") (pintype "passive"))
      (node (ref "U28032") (pin "3") (pinfunction "IN3_3") (pintype "input"))
    )
    (net (code "180") (name "Net-(U28032-IN4)") (class "Default")
      (node (ref "R42802") (pin "1") (pinfunction "1_1") (pintype "passive"))
      (node (ref "U28032") (pin "4") (pinfunction "IN4_4") (pintype "input"))
    )
    (net (code "181") (name "Net-(U28032-IN5)") (class "Default")
      (node (ref "R528032") (pin "1") (pinfunction "1_1") (pintype "passive"))
      (node (ref "U28032") (pin "5") (pinfunction "IN5_5") (pintype "input"))
    )
    (net (code "182") (name "Net-(U28032-IN6)") (class "Default")
      (node (ref "R628032") (pin "1") (pinfunction "1_1") (pintype "passive"))
      (node (ref "U28032") (pin "6") (pinfunction "IN6_6") (pintype "input"))
    )
    (net (code "183") (name "Net-(U28032-IN7)") (class "Default")
      (node (ref "R728032") (pin "1") (pinfunction "1_1") (pintype "passive"))
      (node (ref "U28032") (pin "7") (pinfunction "IN7_7") (pintype "input"))
    )
    (net (code "184") (name "Net-(U28032-IN8)") (class "Default")
      (node (ref "R828032") (pin "1") (pinfunction "1_1") (pintype "passive"))
      (node (ref "U28032") (pin "8") (pinfunction "IN8_8") (pintype "input"))
    )
    (net (code "185") (name "Net-(U28033-IN1)") (class "Default")
      (node (ref "R128033") (pin "1") (pinfunction "1_1") (pintype "passive"))
      (node (ref "U28033") (pin "1") (pinfunction "IN1_1") (pintype "input"))
    )
    (net (code "186") (name "Net-(U28033-IN2)") (class "Default")
      (node (ref "R228033") (pin "1") (pinfunction "1_1") (pintype "passive"))
      (node (ref "U28033") (pin "2") (pinfunction "IN2_2") (pintype "input"))
    )
    (net (code "187") (name "Net-(U28033-IN3)") (class "Default")
      (node (ref "R328033") (pin "1") (pinfunction "1_1") (pintype "passive"))
      (node (ref "U28033") (pin "3") (pinfunction "IN3_3") (pintype "input"))
    )
    (net (code "188") (name "Net-(U28033-IN4)") (class "Default")
      (node (ref "R42803") (pin "1") (pinfunction "1_1") (pintype "passive"))
      (node (ref "U28033") (pin "4") (pinfunction "IN4_4") (pintype "input"))
    )
    (net (code "189") (name "Net-(U28033-IN5)") (class "Default")
      (node (ref "R528033") (pin "1") (pinfunction "1_1") (pintype "passive"))
      (node (ref "U28033") (pin "5") (pinfunction "IN5_5") (pintype "input"))
    )
    (net (code "190") (name "Net-(U28033-IN6)") (class "Default")
      (node (ref "R628033") (pin "1") (pinfunction "1_1") (pintype "passive"))
      (node (ref "U28033") (pin "6") (pinfunction "IN6_6") (pintype "input"))
    )
    (net (code "191") (name "Net-(U28033-IN7)") (class "Default")
      (node (ref "R728033") (pin "1") (pinfunction "1_1") (pintype "passive"))
      (node (ref "U28033") (pin "7") (pinfunction "IN7_7") (pintype "input"))
    )
    (net (code "192") (name "Net-(U28033-IN8)") (class "Default")
      (node (ref "R828033") (pin "1") (pinfunction "1_1") (pintype "passive"))
      (node (ref "U28033") (pin "8") (pinfunction "IN8_8") (pintype "input"))
    )
    (net (code "193") (name "Net-(U28034-IN1)") (class "Default")
      (node (ref "R128034") (pin "1") (pinfunction "1_1") (pintype "passive"))
      (node (ref "U28034") (pin "1") (pinfunction "IN1_1") (pintype "input"))
    )
    (net (code "194") (name "Net-(U28034-IN2)") (class "Default")
      (node (ref "R228034") (pin "1") (pinfunction "1_1") (pintype "passive"))
      (node (ref "U28034") (pin "2") (pinfunction "IN2_2") (pintype "input"))
    )
    (net (code "195") (name "Net-(U28034-IN3)") (class "Default")
      (node (ref "R328034") (pin "1") (pinfunction "1_1") (pintype "passive"))
      (node (ref "U28034") (pin "3") (pinfunction "IN3_3") (pintype "input"))
    )
    (net (code "196") (name "Net-(U28034-IN4)") (class "Default")
      (node (ref "R42804") (pin "1") (pinfunction "1_1") (pintype "passive"))
      (node (ref "U28034") (pin "4") (pinfunction "IN4_4") (pintype "input"))
    )
    (net (code "197") (name "Net-(U28034-IN5)") (class "Default")
      (node (ref "R528034") (pin "1") (pinfunction "1_1") (pintype "passive"))
      (node (ref "U28034") (pin "5") (pinfunction "IN5_5") (pintype "input"))
    )
    (net (code "198") (name "Net-(U28034-IN6)") (class "Default")
      (node (ref "R628034") (pin "1") (pinfunction "1_1") (pintype "passive"))
      (node (ref "U28034") (pin "6") (pinfunction "IN6_6") (pintype "input"))
    )
    (net (code "199") (name "Net-(U28034-IN7)") (class "Default")
      (node (ref "R728034") (pin "1") (pinfunction "1_1") (pintype "passive"))
      (node (ref "U28034") (pin "7") (pinfunction "IN7_7") (pintype "input"))
    )
    (net (code "200") (name "Net-(U28034-IN8)") (class "Default")
      (node (ref "R828034") (pin "1") (pinfunction "1_1") (pintype "passive"))
      (node (ref "U28034") (pin "8") (pinfunction "IN8_8") (pintype "input"))
    )
    (net (code "201") (name "Net-(U28035-IN1)") (class "Default")
      (node (ref "R128035") (pin "1") (pinfunction "1_1") (pintype "passive"))
      (node (ref "U28035") (pin "1") (pinfunction "IN1_1") (pintype "input"))
    )
    (net (code "202") (name "Net-(U28035-IN2)") (class "Default")
      (node (ref "R228035") (pin "1") (pinfunction "1_1") (pintype "passive"))
      (node (ref "U28035") (pin "2") (pinfunction "IN2_2") (pintype "input"))
    )
    (net (code "203") (name "Net-(U28035-IN3)") (class "Default")
      (node (ref "R328035") (pin "1") (pinfunction "1_1") (pintype "passive"))
      (node (ref "U28035") (pin "3") (pinfunction "IN3_3") (pintype "input"))
    )
    (net (code "204") (name "Net-(U28035-IN4)") (class "Default")
      (node (ref "R428035") (pin "1") (pinfunction "1_1") (pintype "passive"))
      (node (ref "U28035") (pin "4") (pinfunction "IN4_4") (pintype "input"))
    )
    (net (code "205") (name "Net-(U28035-IN5)") (class "Default")
      (node (ref "R528035") (pin "1") (pinfunction "1_1") (pintype "passive"))
      (node (ref "U28035") (pin "5") (pinfunction "IN5_5") (pintype "input"))
    )
    (net (code "206") (name "Net-(U28035-IN6)") (class "Default")
      (node (ref "R628035") (pin "1") (pinfunction "1_1") (pintype "passive"))
      (node (ref "U28035") (pin "6") (pinfunction "IN6_6") (pintype "input"))
    )
    (net (code "207") (name "Net-(U28035-IN7)") (class "Default")
      (node (ref "R728035") (pin "1") (pinfunction "1_1") (pintype "passive"))
      (node (ref "U28035") (pin "7") (pinfunction "IN7_7") (pintype "input"))
    )
    (net (code "208") (name "Net-(U28035-IN8)") (class "Default")
      (node (ref "R828035") (pin "1") (pinfunction "1_1") (pintype "passive"))
      (node (ref "U28035") (pin "8") (pinfunction "IN8_8") (pintype "input"))
    )
    (net (code "209") (name "VCC") (class "Default")
      (node (ref "C081") (pin "1") (pinfunction "1_1") (pintype "passive"))
      (node (ref "C082") (pin "1") (pinfunction "1_1") (pintype "passive"))
      (node (ref "C1511") (pin "1") (pinfunction "1_1") (pintype "passive"))
      (node (ref "C1512") (pin "1") (pinfunction "1_1") (pintype "passive"))
      (node (ref "C1513") (pin "1") (pinfunction "1_1") (pintype "passive"))
      (node (ref "C1514") (pin "1") (pinfunction "1_1") (pintype "passive"))
      (node (ref "C1515") (pin "1") (pinfunction "1_1") (pintype "passive"))
      (node (ref "C1P") (pin "1") (pinfunction "1_1") (pintype "passive"))
      (node (ref "P031") (pin "9") (pinfunction "9_9") (pintype "passive"))
      (node (ref "P032") (pin "9") (pinfunction "9_9") (pintype "passive"))
      (node (ref "P033") (pin "9") (pinfunction "9_9") (pintype "passive"))
      (node (ref "P034") (pin "9") (pinfunction "9_9") (pintype "passive"))
      (node (ref "P035") (pin "9") (pinfunction "9_9") (pintype "passive"))
      (node (ref "POWER") (pin "1") (pinfunction "1_1") (pintype "passive"))
      (node (ref "Rp2") (pin "1") (pinfunction "1_1") (pintype "passive"))
      (node (ref "Rx21") (pin "2") (pinfunction "2_2") (pintype "passive"))
      (node (ref "U081") (pin "14") (pinfunction "VCC_14") (pintype "power_in"))
      (node (ref "U082") (pin "14") (pinfunction "VCC_14") (pintype "power_in"))
      (node (ref "U1511") (pin "16") (pinfunction "VCC_16") (pintype "power_in"))
      (node (ref "U1512") (pin "16") (pinfunction "VCC_16") (pintype "power_in"))
      (node (ref "U1513") (pin "16") (pinfunction "VCC_16") (pintype "power_in"))
      (node (ref "U1514") (pin "16") (pinfunction "VCC_16") (pintype "power_in"))
      (node (ref "U1515") (pin "16") (pinfunction "VCC_16") (pintype "power_in"))
      (node (ref "U28031") (pin "10") (pinfunction "COM_D_10") (pintype "passive"))
      (node (ref "U28032") (pin "10") (pinfunction "COM_D_10") (pintype "passive"))
      (node (ref "U28033") (pin "10") (pinfunction "COM_D_10") (pintype "passive"))
      (node (ref "U28034") (pin "10") (pinfunction "COM_D_10") (pintype "passive"))
      (node (ref "U28035") (pin "10") (pinfunction "COM_D_10") (pintype "passive"))
    )
    (net (code "210") (name "unconnected-(U1-RA2{slash}AN2{slash}VREF--Pad4)") (class "Default")
      (node (ref "U1") (pin "4") (pinfunction "RA2/AN2/VREF-_4") (pintype "bidirectional+no_connect"))
    )
    (net (code "211") (name "unconnected-(U1-RA3{slash}AN3{slash}VREF+-Pad5)") (class "Default")
      (node (ref "U1") (pin "5") (pinfunction "RA3/AN3/VREF+_5") (pintype "bidirectional+no_connect"))
    )
    (net (code "212") (name "unconnected-(U1-RA4{slash}T0CKI-Pad6)") (class "Default")
      (node (ref "U1") (pin "6") (pinfunction "RA4/T0CKI_6") (pintype "bidirectional+no_connect"))
    )
    (net (code "213") (name "unconnected-(U1-RA5{slash}AN4{slash}~{SS}{slash}LVDIN-Pad7)") (class "Default")
      (node (ref "U1") (pin "7") (pinfunction "RA5/AN4/~{SS}/LVDIN_7") (pintype "bidirectional+no_connect"))
    )
    (net (code "214") (name "unconnected-(U1-RC5{slash}SDO-Pad16)") (class "Default")
      (node (ref "U1") (pin "16") (pinfunction "RC5/SDO_16") (pintype "bidirectional"))
    )
    (net (code "215") (name "unconnected-(U1511-W-Pad6)") (class "Default")
      (node (ref "U1511") (pin "6") (pinfunction "W_6") (pintype "output"))
    )
    (net (code "216") (name "unconnected-(U1512-W-Pad6)") (class "Default")
      (node (ref "U1512") (pin "6") (pinfunction "W_6") (pintype "output"))
    )
    (net (code "217") (name "unconnected-(U1513-W-Pad6)") (class "Default")
      (node (ref "U1513") (pin "6") (pinfunction "W_6") (pintype "output"))
    )
    (net (code "218") (name "unconnected-(U1514-W-Pad6)") (class "Default")
      (node (ref "U1514") (pin "6") (pinfunction "W_6") (pintype "output"))
    )
    (net (code "219") (name "unconnected-(U1515-W-Pad6)") (class "Default")
      (node (ref "U1515") (pin "6") (pinfunction "W_6") (pintype "output"))
    )
  )
)
